# BMS_MAINBOARD.net
KiCad netlist of a schematic drawn in Altium Designer
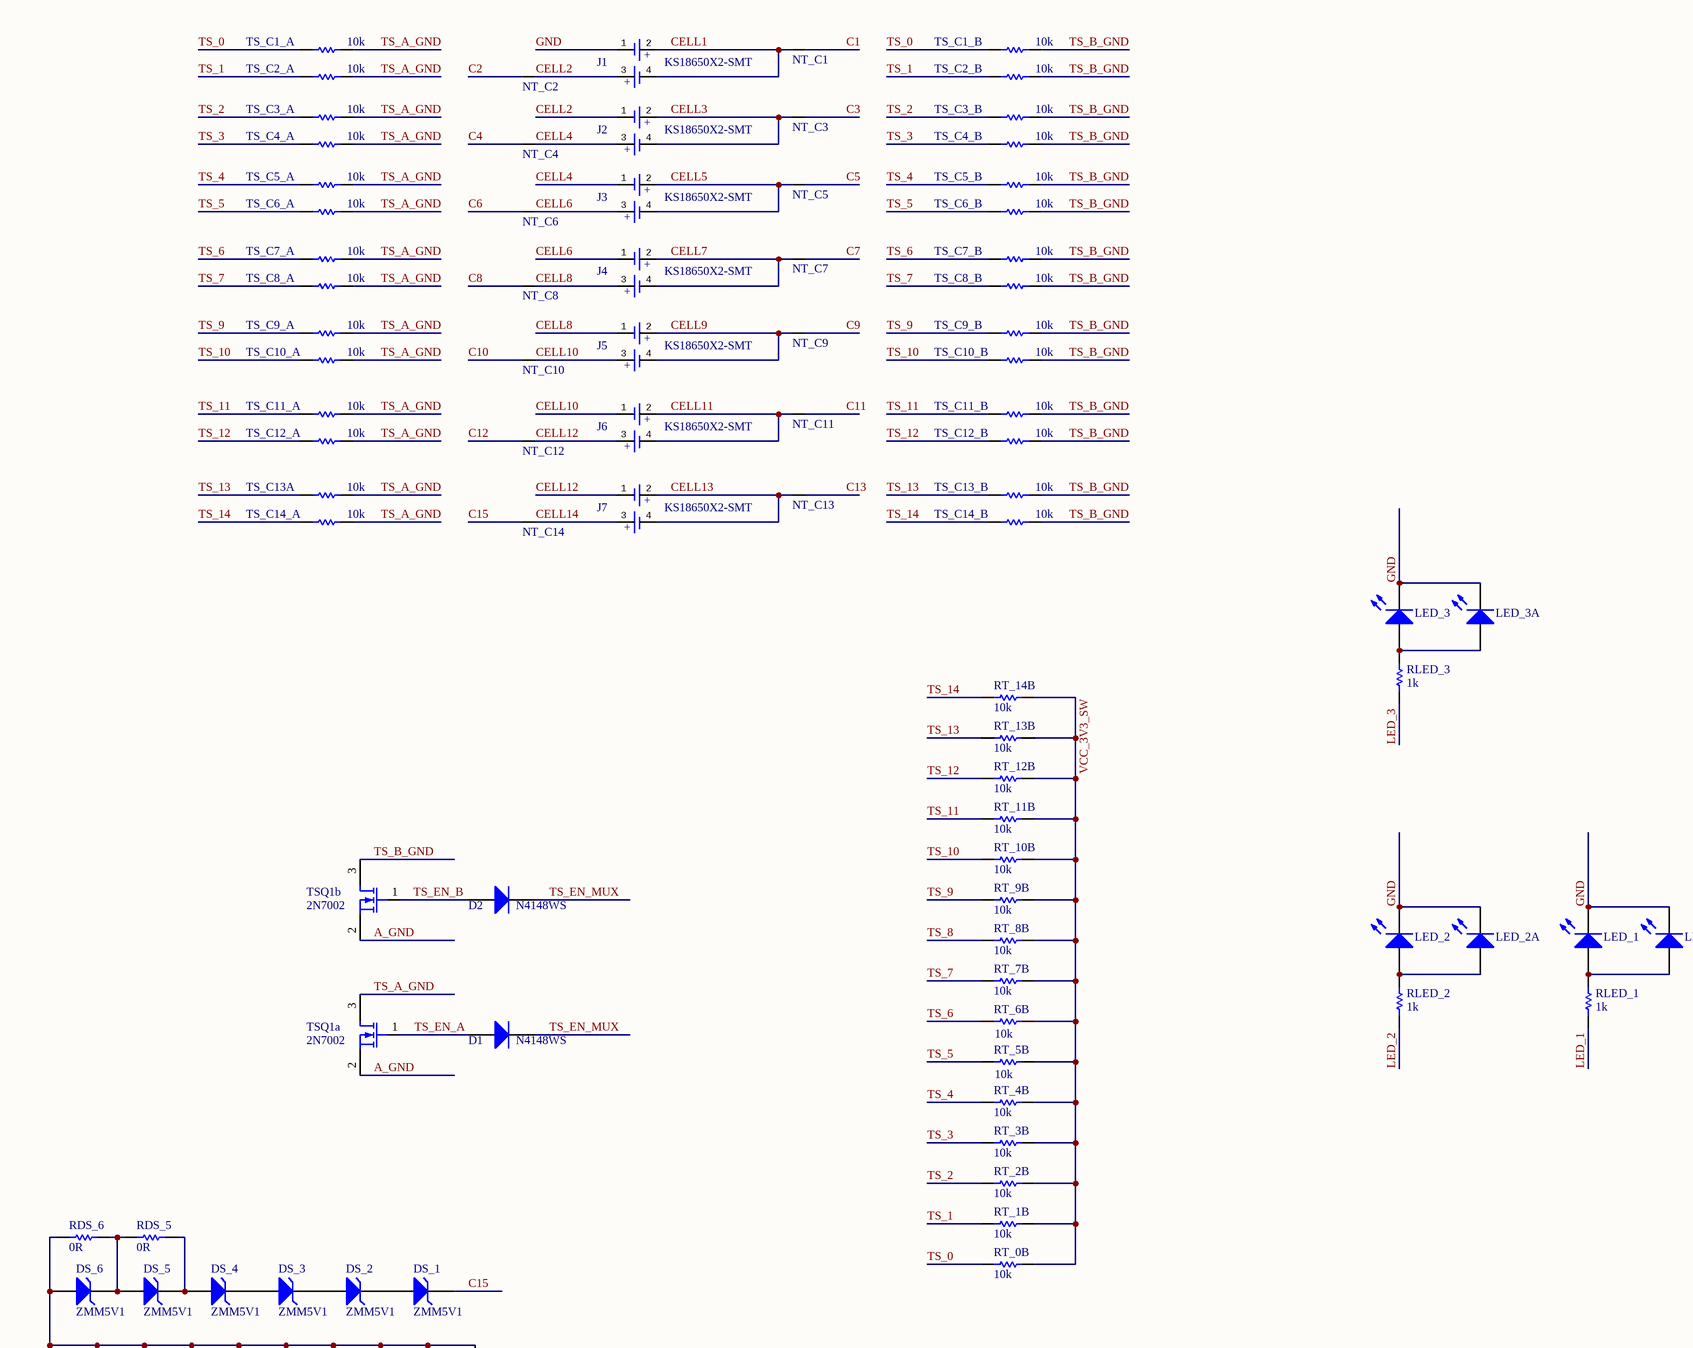
[diagram p0: BMS_MAINBOARD.SchDoc, top left]
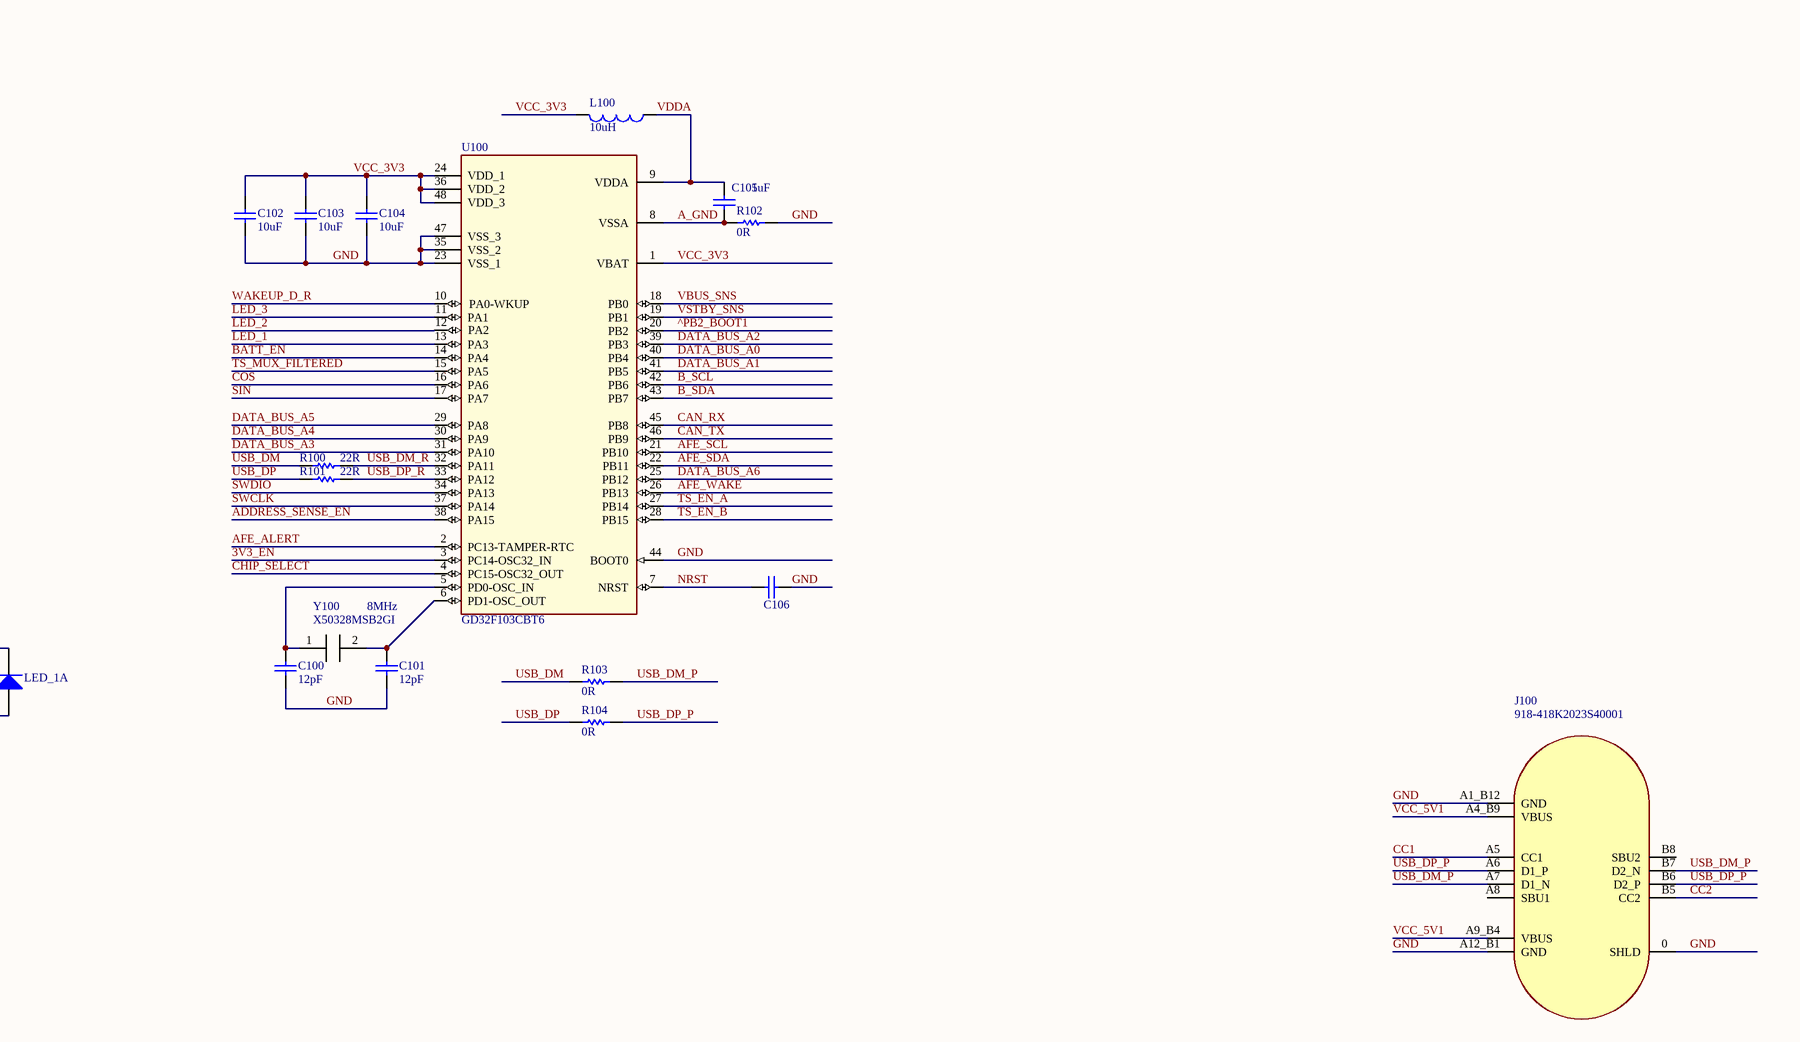
[diagram p1: BMS_MAINBOARD.SchDoc, top right]
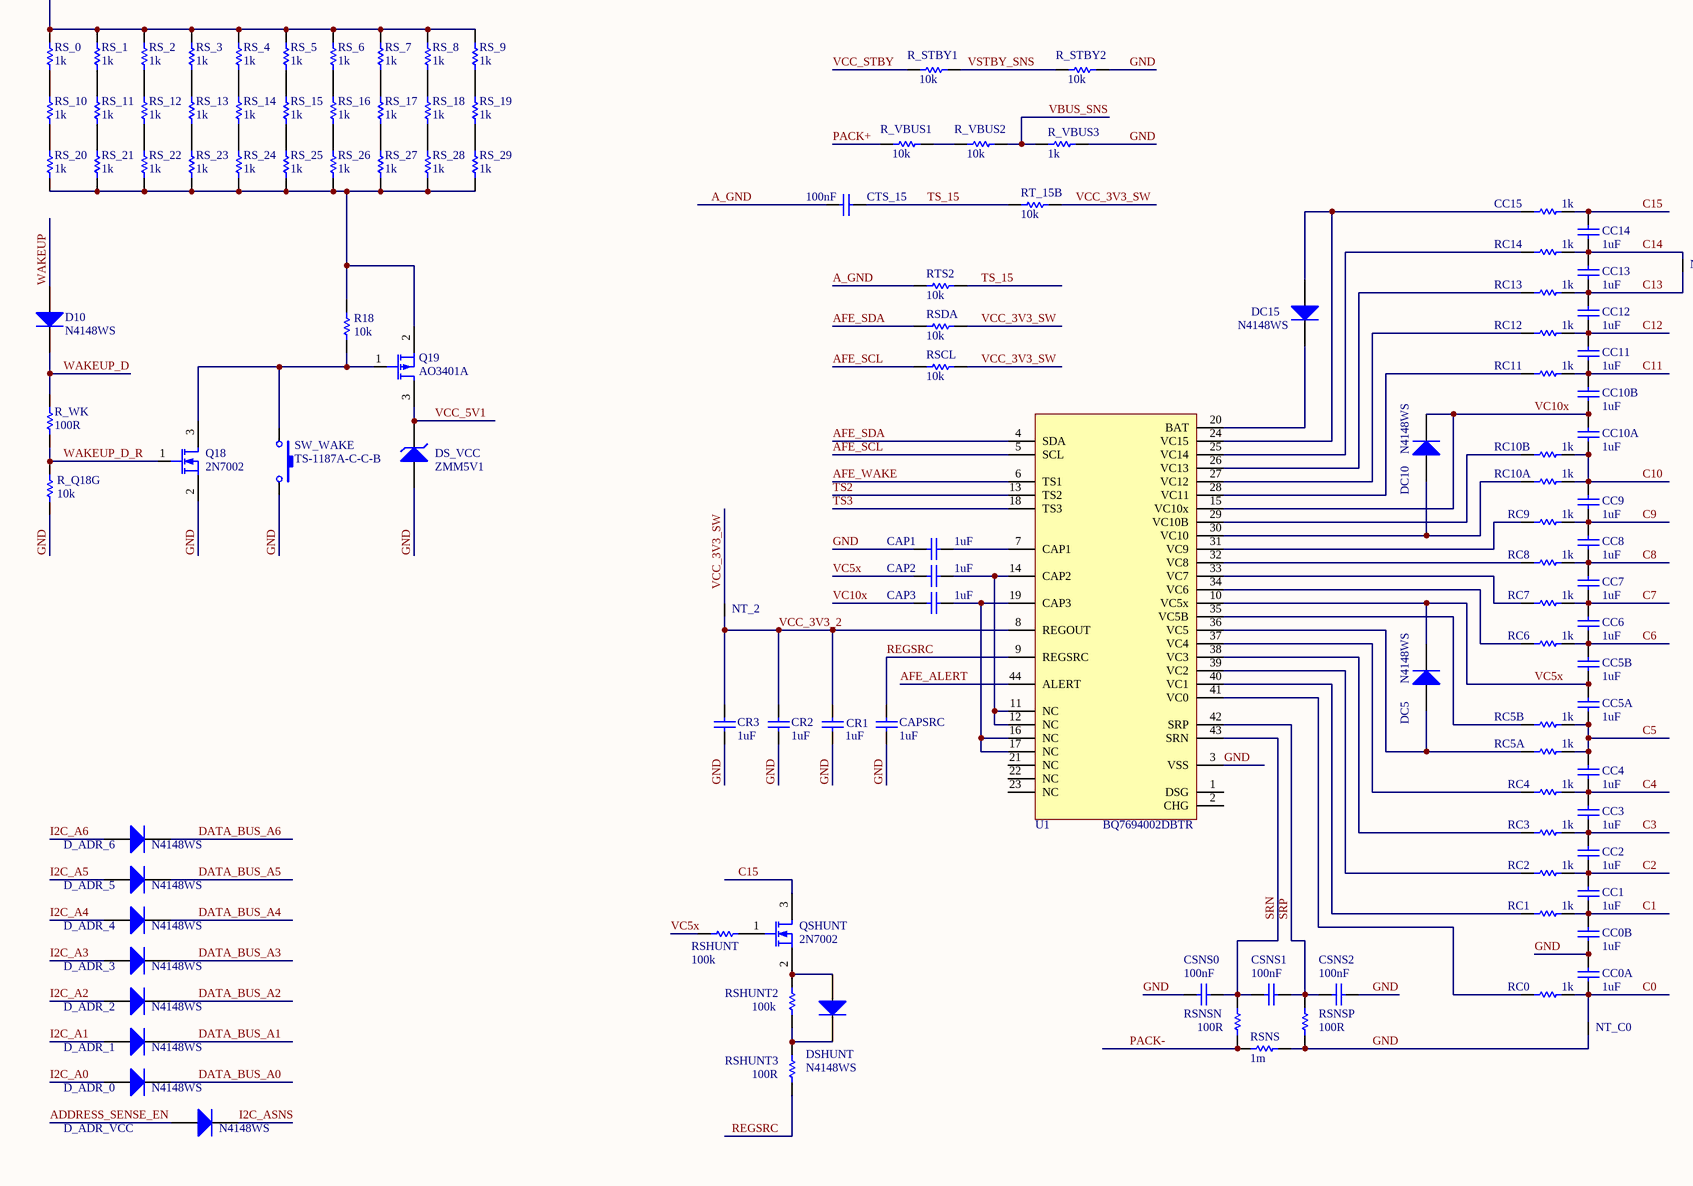
[diagram p2: BMS_MAINBOARD.SchDoc, bottom left]
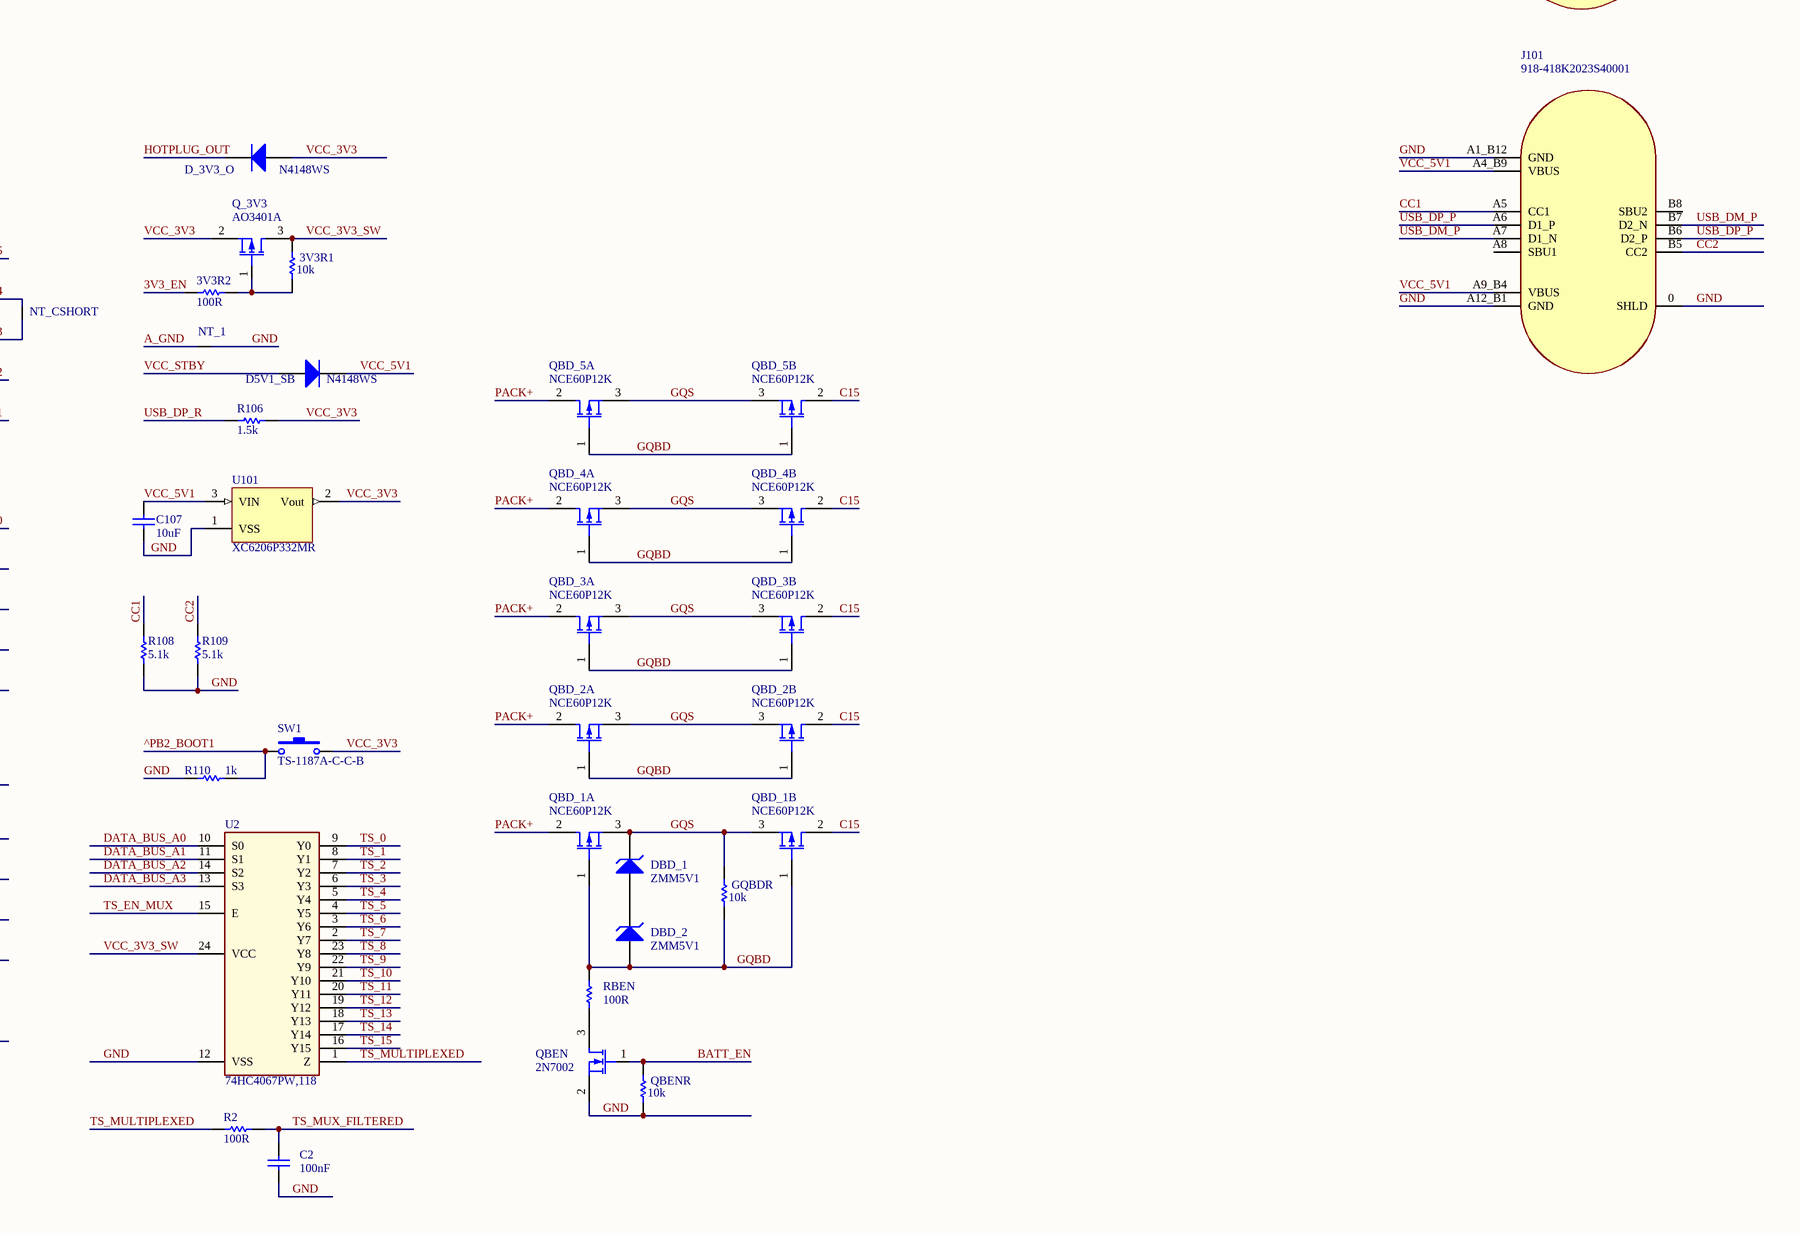
[diagram p3: BMS_MAINBOARD.SchDoc, bottom right]

(export (version "E")
  (design (tool "Eeschema 10.0.6"))
  (components
    (comp (ref "3V3R1")
      (value "10k")
      (footprint "R_0402")
      (description "R - RESISTOR - SMD - 10k - 1% - 0402")
      (fields (field (name "LCSC PART #") "C25744") (field (name "Comment") "0402WGF1002TCE"))
      (libsource (lib "JLC_PCB") (part "0402WGF1002TCE"))
    )
    (comp (ref "3V3R2")
      (value "100R")
      (footprint "R_0402")
      (description "R - RESISTOR - SMD - 100R - 1% - 0402")
      (fields (field (name "LCSC PART #") "C25076") (field (name "Comment") "0402WGF1000TCE"))
      (libsource (lib "JLC_PCB") (part "0402WGF1000TCE"))
    )
    (comp (ref "C2")
      (value "100nF")
      (footprint "C_0402")
      (description "C - CAPACITOR - MLCC - 100nF - 16V - 0402")
      (fields (field (name "LCSC PART #") "C1525") (field (name "Comment") "CL05B104KO5NNNC"))
      (libsource (lib "JLC_PCB") (part "CL05B104KO5NNNC"))
    )
    (comp (ref "C100")
      (value "12pF")
      (footprint "C_0402")
      (description "C - CAPACITOR - MLCC - 12pF - 50V - 0402")
      (fields (field (name "LCSC PART #") "C1547") (field (name "Comment") "0402CG120J500NT"))
      (libsource (lib "JLC_PCB") (part "0402CG120J500NT"))
    )
    (comp (ref "C101")
      (value "12pF")
      (footprint "C_0402")
      (description "C - CAPACITOR - MLCC - 12pF - 50V - 0402")
      (fields (field (name "LCSC PART #") "C1547") (field (name "Comment") "0402CG120J500NT"))
      (libsource (lib "JLC_PCB") (part "0402CG120J500NT"))
    )
    (comp (ref "C102")
      (value "10uF")
      (footprint "C_0402")
      (description "C - CAPACITOR - MLCC - 10uF - 6.3V - 0402")
      (fields (field (name "LCSC PART #") "C15525") (field (name "Comment") "CL05A106MQ5NUNC"))
      (libsource (lib "JLC_PCB") (part "CL05A106MQ5NUNC"))
    )
    (comp (ref "C103")
      (value "10uF")
      (footprint "C_0402")
      (description "C - CAPACITOR - MLCC - 10uF - 6.3V - 0402")
      (fields (field (name "LCSC PART #") "C15525") (field (name "Comment") "CL05A106MQ5NUNC"))
      (libsource (lib "JLC_PCB") (part "CL05A106MQ5NUNC"))
    )
    (comp (ref "C104")
      (value "10uF")
      (footprint "C_0402")
      (description "C - CAPACITOR - MLCC - 10uF - 6.3V - 0402")
      (fields (field (name "LCSC PART #") "C15525") (field (name "Comment") "CL05A106MQ5NUNC"))
      (libsource (lib "JLC_PCB") (part "CL05A106MQ5NUNC"))
    )
    (comp (ref "C105")
      (value "1uF")
      (footprint "C_0402")
      (description "C - CAPACITOR - MLCC - 1uF - 25V - 0402")
      (fields (field (name "LCSC PART #") "C52923") (field (name "Comment") "CL05A105KA5NQNC"))
      (libsource (lib "JLC_PCB") (part "CL05A105KA5NQNC"))
    )
    (comp (ref "C106")
      (value "0402CG101J500NT")
      (footprint "C_0402")
      (description "C - CAPACITOR - MLCC - 100pF - 50V - 0402")
      (fields (field (name "LCSC PART #") "C1546"))
      (libsource (lib "JLC_PCB") (part "0402CG101J500NT"))
    )
    (comp (ref "C107")
      (value "10uF")
      (footprint "C_0402")
      (description "C - CAPACITOR - MLCC - 10uF - 6.3V - 0402")
      (fields (field (name "LCSC PART #") "C15525") (field (name "Comment") "CL05A106MQ5NUNC"))
      (libsource (lib "JLC_PCB") (part "CL05A106MQ5NUNC"))
    )
    (comp (ref "CAP1")
      (value "1uF")
      (footprint "C_0402")
      (description "C - CAPACITOR - MLCC - 1uF - 25V - 0402")
      (fields (field (name "LCSC PART #") "C52923") (field (name "Comment") "CL05A105KA5NQNC"))
      (libsource (lib "JLC_PCB") (part "CL05A105KA5NQNC"))
    )
    (comp (ref "CAP2")
      (value "1uF")
      (footprint "C_0402")
      (description "C - CAPACITOR - MLCC - 1uF - 25V - 0402")
      (fields (field (name "LCSC PART #") "C52923") (field (name "Comment") "CL05A105KA5NQNC"))
      (libsource (lib "JLC_PCB") (part "CL05A105KA5NQNC"))
    )
    (comp (ref "CAP3")
      (value "1uF")
      (footprint "C_0402")
      (description "C - CAPACITOR - MLCC - 1uF - 25V - 0402")
      (fields (field (name "LCSC PART #") "C52923") (field (name "Comment") "CL05A105KA5NQNC"))
      (libsource (lib "JLC_PCB") (part "CL05A105KA5NQNC"))
    )
    (comp (ref "CAPSRC")
      (value "1uF")
      (footprint "C_0402")
      (description "C - CAPACITOR - MLCC - 1uF - 25V - 0402")
      (fields (field (name "LCSC PART #") "C52923") (field (name "Comment") "CL05A105KA5NQNC"))
      (libsource (lib "JLC_PCB") (part "CL05A105KA5NQNC"))
    )
    (comp (ref "CC0A")
      (value "1uF")
      (footprint "C_0402")
      (description "C - CAPACITOR - MLCC - 1uF - 25V - 0402")
      (fields (field (name "LCSC PART #") "C52923") (field (name "Comment") "CL05A105KA5NQNC"))
      (libsource (lib "JLC_PCB") (part "CL05A105KA5NQNC"))
    )
    (comp (ref "CC0B")
      (value "1uF")
      (footprint "C_0402")
      (description "C - CAPACITOR - MLCC - 1uF - 25V - 0402")
      (fields (field (name "LCSC PART #") "C52923") (field (name "Comment") "CL05A105KA5NQNC"))
      (libsource (lib "JLC_PCB") (part "CL05A105KA5NQNC"))
    )
    (comp (ref "CC1")
      (value "1uF")
      (footprint "C_0402")
      (description "C - CAPACITOR - MLCC - 1uF - 25V - 0402")
      (fields (field (name "LCSC PART #") "C52923") (field (name "Comment") "CL05A105KA5NQNC"))
      (libsource (lib "JLC_PCB") (part "CL05A105KA5NQNC"))
    )
    (comp (ref "CC2")
      (value "1uF")
      (footprint "C_0402")
      (description "C - CAPACITOR - MLCC - 1uF - 25V - 0402")
      (fields (field (name "LCSC PART #") "C52923") (field (name "Comment") "CL05A105KA5NQNC"))
      (libsource (lib "JLC_PCB") (part "CL05A105KA5NQNC"))
    )
    (comp (ref "CC3")
      (value "1uF")
      (footprint "C_0402")
      (description "C - CAPACITOR - MLCC - 1uF - 25V - 0402")
      (fields (field (name "LCSC PART #") "C52923") (field (name "Comment") "CL05A105KA5NQNC"))
      (libsource (lib "JLC_PCB") (part "CL05A105KA5NQNC"))
    )
    (comp (ref "CC4")
      (value "1uF")
      (footprint "C_0402")
      (description "C - CAPACITOR - MLCC - 1uF - 25V - 0402")
      (fields (field (name "LCSC PART #") "C52923") (field (name "Comment") "CL05A105KA5NQNC"))
      (libsource (lib "JLC_PCB") (part "CL05A105KA5NQNC"))
    )
    (comp (ref "CC5A")
      (value "1uF")
      (footprint "C_0402")
      (description "C - CAPACITOR - MLCC - 1uF - 25V - 0402")
      (fields (field (name "LCSC PART #") "C52923") (field (name "Comment") "CL05A105KA5NQNC"))
      (libsource (lib "JLC_PCB") (part "CL05A105KA5NQNC"))
    )
    (comp (ref "CC5B")
      (value "1uF")
      (footprint "C_0402")
      (description "C - CAPACITOR - MLCC - 1uF - 25V - 0402")
      (fields (field (name "LCSC PART #") "C52923") (field (name "Comment") "CL05A105KA5NQNC"))
      (libsource (lib "JLC_PCB") (part "CL05A105KA5NQNC"))
    )
    (comp (ref "CC6")
      (value "1uF")
      (footprint "C_0402")
      (description "C - CAPACITOR - MLCC - 1uF - 25V - 0402")
      (fields (field (name "LCSC PART #") "C52923") (field (name "Comment") "CL05A105KA5NQNC"))
      (libsource (lib "JLC_PCB") (part "CL05A105KA5NQNC"))
    )
    (comp (ref "CC7")
      (value "1uF")
      (footprint "C_0402")
      (description "C - CAPACITOR - MLCC - 1uF - 25V - 0402")
      (fields (field (name "LCSC PART #") "C52923") (field (name "Comment") "CL05A105KA5NQNC"))
      (libsource (lib "JLC_PCB") (part "CL05A105KA5NQNC"))
    )
    (comp (ref "CC8")
      (value "1uF")
      (footprint "C_0402")
      (description "C - CAPACITOR - MLCC - 1uF - 25V - 0402")
      (fields (field (name "LCSC PART #") "C52923") (field (name "Comment") "CL05A105KA5NQNC"))
      (libsource (lib "JLC_PCB") (part "CL05A105KA5NQNC"))
    )
    (comp (ref "CC9")
      (value "1uF")
      (footprint "C_0402")
      (description "C - CAPACITOR - MLCC - 1uF - 25V - 0402")
      (fields (field (name "LCSC PART #") "C52923") (field (name "Comment") "CL05A105KA5NQNC"))
      (libsource (lib "JLC_PCB") (part "CL05A105KA5NQNC"))
    )
    (comp (ref "CC10A")
      (value "1uF")
      (footprint "C_0402")
      (description "C - CAPACITOR - MLCC - 1uF - 25V - 0402")
      (fields (field (name "LCSC PART #") "C52923") (field (name "Comment") "CL05A105KA5NQNC"))
      (libsource (lib "JLC_PCB") (part "CL05A105KA5NQNC"))
    )
    (comp (ref "CC10B")
      (value "1uF")
      (footprint "C_0402")
      (description "C - CAPACITOR - MLCC - 1uF - 25V - 0402")
      (fields (field (name "LCSC PART #") "C52923") (field (name "Comment") "CL05A105KA5NQNC"))
      (libsource (lib "JLC_PCB") (part "CL05A105KA5NQNC"))
    )
    (comp (ref "CC11")
      (value "1uF")
      (footprint "C_0402")
      (description "C - CAPACITOR - MLCC - 1uF - 25V - 0402")
      (fields (field (name "LCSC PART #") "C52923") (field (name "Comment") "CL05A105KA5NQNC"))
      (libsource (lib "JLC_PCB") (part "CL05A105KA5NQNC"))
    )
    (comp (ref "CC12")
      (value "1uF")
      (footprint "C_0402")
      (description "C - CAPACITOR - MLCC - 1uF - 25V - 0402")
      (fields (field (name "LCSC PART #") "C52923") (field (name "Comment") "CL05A105KA5NQNC"))
      (libsource (lib "JLC_PCB") (part "CL05A105KA5NQNC"))
    )
    (comp (ref "CC13")
      (value "1uF")
      (footprint "C_0402")
      (description "C - CAPACITOR - MLCC - 1uF - 25V - 0402")
      (fields (field (name "LCSC PART #") "C52923") (field (name "Comment") "CL05A105KA5NQNC"))
      (libsource (lib "JLC_PCB") (part "CL05A105KA5NQNC"))
    )
    (comp (ref "CC14")
      (value "1uF")
      (footprint "C_0402")
      (description "C - CAPACITOR - MLCC - 1uF - 25V - 0402")
      (fields (field (name "LCSC PART #") "C52923") (field (name "Comment") "CL05A105KA5NQNC"))
      (libsource (lib "JLC_PCB") (part "CL05A105KA5NQNC"))
    )
    (comp (ref "CC15")
      (value "1k")
      (footprint "R_0402")
      (description "R - RESISTOR - SMD - 1k - 1% - 0402")
      (fields (field (name "LCSC PART #") "C11702") (field (name "Comment") "0402WGF1001TCE"))
      (libsource (lib "JLC_PCB") (part "0402WGF1001TCE"))
    )
    (comp (ref "CR1")
      (value "1uF")
      (footprint "C_0402")
      (description "C - CAPACITOR - MLCC - 1uF - 25V - 0402")
      (fields (field (name "LCSC PART #") "C52923") (field (name "Comment") "CL05A105KA5NQNC"))
      (libsource (lib "JLC_PCB") (part "CL05A105KA5NQNC"))
    )
    (comp (ref "CR2")
      (value "1uF")
      (footprint "C_0402")
      (description "C - CAPACITOR - MLCC - 1uF - 25V - 0402")
      (fields (field (name "LCSC PART #") "C52923") (field (name "Comment") "CL05A105KA5NQNC"))
      (libsource (lib "JLC_PCB") (part "CL05A105KA5NQNC"))
    )
    (comp (ref "CR3")
      (value "1uF")
      (footprint "C_0402")
      (description "C - CAPACITOR - MLCC - 1uF - 25V - 0402")
      (fields (field (name "LCSC PART #") "C52923") (field (name "Comment") "CL05A105KA5NQNC"))
      (libsource (lib "JLC_PCB") (part "CL05A105KA5NQNC"))
    )
    (comp (ref "CSNS0")
      (value "100nF")
      (footprint "C_0402")
      (description "C - CAPACITOR - MLCC - 100nF - 16V - 0402")
      (fields (field (name "LCSC PART #") "C1525") (field (name "Comment") "CL05B104KO5NNNC"))
      (libsource (lib "JLC_PCB") (part "CL05B104KO5NNNC"))
    )
    (comp (ref "CSNS1")
      (value "100nF")
      (footprint "C_0402")
      (description "C - CAPACITOR - MLCC - 100nF - 16V - 0402")
      (fields (field (name "LCSC PART #") "C1525") (field (name "Comment") "CL05B104KO5NNNC"))
      (libsource (lib "JLC_PCB") (part "CL05B104KO5NNNC"))
    )
    (comp (ref "CSNS2")
      (value "100nF")
      (footprint "C_0402")
      (description "C - CAPACITOR - MLCC - 100nF - 16V - 0402")
      (fields (field (name "LCSC PART #") "C1525") (field (name "Comment") "CL05B104KO5NNNC"))
      (libsource (lib "JLC_PCB") (part "CL05B104KO5NNNC"))
    )
    (comp (ref "CTS_15")
      (value "100nF")
      (footprint "C_0402")
      (description "C - CAPACITOR - MLCC - 100nF - 16V - 0402")
      (fields (field (name "LCSC PART #") "C1525") (field (name "Comment") "CL05B104KO5NNNC"))
      (libsource (lib "JLC_PCB") (part "CL05B104KO5NNNC"))
    )
    (comp (ref "D1")
      (value "N4148WS")
      (footprint "SOD-323")
      (description "D - DIODE - FAST TRR - 100V - 150mA - 4ns")
      (fields (field (name "LCSC PART #") "C2128"))
      (libsource (lib "JLC_PCB") (part "N4148WS"))
    )
    (comp (ref "D2")
      (value "N4148WS")
      (footprint "SOD-323")
      (description "D - DIODE - FAST TRR - 100V - 150mA - 4ns")
      (fields (field (name "LCSC PART #") "C2128"))
      (libsource (lib "JLC_PCB") (part "N4148WS"))
    )
    (comp (ref "D5V1_SB")
      (value "N4148WS")
      (footprint "SOD-323")
      (description "D - DIODE - FAST TRR - 100V - 150mA - 4ns")
      (fields (field (name "LCSC PART #") "C2128"))
      (libsource (lib "JLC_PCB") (part "N4148WS"))
    )
    (comp (ref "D10")
      (value "N4148WS")
      (footprint "SOD-323")
      (description "D - DIODE - FAST TRR - 100V - 150mA - 4ns")
      (fields (field (name "LCSC PART #") "C2128"))
      (libsource (lib "JLC_PCB") (part "N4148WS"))
    )
    (comp (ref "DBD_1")
      (value "ZMM5V1")
      (footprint "DO-213AA")
      (description "D - DIODE - ZENER - 5.1V - 500mW")
      (fields (field (name "LCSC PART #") "C8061"))
      (libsource (lib "JLC_PCB") (part "ZMM5V1"))
    )
    (comp (ref "DBD_2")
      (value "ZMM5V1")
      (footprint "DO-213AA")
      (description "D - DIODE - ZENER - 5.1V - 500mW")
      (fields (field (name "LCSC PART #") "C8061"))
      (libsource (lib "JLC_PCB") (part "ZMM5V1"))
    )
    (comp (ref "DC5")
      (value "N4148WS")
      (footprint "SOD-323")
      (description "D - DIODE - FAST TRR - 100V - 150mA - 4ns")
      (fields (field (name "LCSC PART #") "C2128"))
      (libsource (lib "JLC_PCB") (part "N4148WS"))
    )
    (comp (ref "DC10")
      (value "N4148WS")
      (footprint "SOD-323")
      (description "D - DIODE - FAST TRR - 100V - 150mA - 4ns")
      (fields (field (name "LCSC PART #") "C2128"))
      (libsource (lib "JLC_PCB") (part "N4148WS"))
    )
    (comp (ref "DC15")
      (value "N4148WS")
      (footprint "SOD-323")
      (description "D - DIODE - FAST TRR - 100V - 150mA - 4ns")
      (fields (field (name "LCSC PART #") "C2128"))
      (libsource (lib "JLC_PCB") (part "N4148WS"))
    )
    (comp (ref "DSHUNT")
      (value "N4148WS")
      (footprint "SOD-323")
      (description "D - DIODE - FAST TRR - 100V - 150mA - 4ns")
      (fields (field (name "LCSC PART #") "C2128"))
      (libsource (lib "JLC_PCB") (part "N4148WS"))
    )
    (comp (ref "DS_1")
      (value "ZMM5V1")
      (footprint "DO-213AA")
      (description "D - DIODE - ZENER - 5.1V - 500mW")
      (fields (field (name "LCSC PART #") "C8061"))
      (libsource (lib "JLC_PCB") (part "ZMM5V1"))
    )
    (comp (ref "DS_2")
      (value "ZMM5V1")
      (footprint "DO-213AA")
      (description "D - DIODE - ZENER - 5.1V - 500mW")
      (fields (field (name "LCSC PART #") "C8061"))
      (libsource (lib "JLC_PCB") (part "ZMM5V1"))
    )
    (comp (ref "DS_3")
      (value "ZMM5V1")
      (footprint "DO-213AA")
      (description "D - DIODE - ZENER - 5.1V - 500mW")
      (fields (field (name "LCSC PART #") "C8061"))
      (libsource (lib "JLC_PCB") (part "ZMM5V1"))
    )
    (comp (ref "DS_4")
      (value "ZMM5V1")
      (footprint "DO-213AA")
      (description "D - DIODE - ZENER - 5.1V - 500mW")
      (fields (field (name "LCSC PART #") "C8061"))
      (libsource (lib "JLC_PCB") (part "ZMM5V1"))
    )
    (comp (ref "DS_5")
      (value "ZMM5V1")
      (footprint "DO-213AA")
      (description "D - DIODE - ZENER - 5.1V - 500mW")
      (fields (field (name "LCSC PART #") "C8061"))
      (libsource (lib "JLC_PCB") (part "ZMM5V1"))
    )
    (comp (ref "DS_6")
      (value "ZMM5V1")
      (footprint "DO-213AA")
      (description "D - DIODE - ZENER - 5.1V - 500mW")
      (fields (field (name "LCSC PART #") "C8061"))
      (libsource (lib "JLC_PCB") (part "ZMM5V1"))
    )
    (comp (ref "DS_VCC")
      (value "ZMM5V1")
      (footprint "DO-213AA")
      (description "D - DIODE - ZENER - 5.1V - 500mW")
      (fields (field (name "LCSC PART #") "C8061"))
      (libsource (lib "JLC_PCB") (part "ZMM5V1"))
    )
    (comp (ref "D_3V3_O")
      (value "N4148WS")
      (footprint "SOD-323")
      (description "D - DIODE - FAST TRR - 100V - 150mA - 4ns")
      (fields (field (name "LCSC PART #") "C2128"))
      (libsource (lib "JLC_PCB") (part "N4148WS"))
    )
    (comp (ref "D_ADR_0")
      (value "N4148WS")
      (footprint "SOD-323")
      (description "D - DIODE - FAST TRR - 100V - 150mA - 4ns")
      (fields (field (name "LCSC PART #") "C2128"))
      (libsource (lib "JLC_PCB") (part "N4148WS"))
    )
    (comp (ref "D_ADR_1")
      (value "N4148WS")
      (footprint "SOD-323")
      (description "D - DIODE - FAST TRR - 100V - 150mA - 4ns")
      (fields (field (name "LCSC PART #") "C2128"))
      (libsource (lib "JLC_PCB") (part "N4148WS"))
    )
    (comp (ref "D_ADR_2")
      (value "N4148WS")
      (footprint "SOD-323")
      (description "D - DIODE - FAST TRR - 100V - 150mA - 4ns")
      (fields (field (name "LCSC PART #") "C2128"))
      (libsource (lib "JLC_PCB") (part "N4148WS"))
    )
    (comp (ref "D_ADR_3")
      (value "N4148WS")
      (footprint "SOD-323")
      (description "D - DIODE - FAST TRR - 100V - 150mA - 4ns")
      (fields (field (name "LCSC PART #") "C2128"))
      (libsource (lib "JLC_PCB") (part "N4148WS"))
    )
    (comp (ref "D_ADR_4")
      (value "N4148WS")
      (footprint "SOD-323")
      (description "D - DIODE - FAST TRR - 100V - 150mA - 4ns")
      (fields (field (name "LCSC PART #") "C2128"))
      (libsource (lib "JLC_PCB") (part "N4148WS"))
    )
    (comp (ref "D_ADR_5")
      (value "N4148WS")
      (footprint "SOD-323")
      (description "D - DIODE - FAST TRR - 100V - 150mA - 4ns")
      (fields (field (name "LCSC PART #") "C2128"))
      (libsource (lib "JLC_PCB") (part "N4148WS"))
    )
    (comp (ref "D_ADR_6")
      (value "N4148WS")
      (footprint "SOD-323")
      (description "D - DIODE - FAST TRR - 100V - 150mA - 4ns")
      (fields (field (name "LCSC PART #") "C2128"))
      (libsource (lib "JLC_PCB") (part "N4148WS"))
    )
    (comp (ref "D_ADR_VCC")
      (value "N4148WS")
      (footprint "SOD-323")
      (description "D - DIODE - FAST TRR - 100V - 150mA - 4ns")
      (fields (field (name "LCSC PART #") "C2128"))
      (libsource (lib "JLC_PCB") (part "N4148WS"))
    )
    (comp (ref "GQBDR")
      (value "10k")
      (footprint "R_0402")
      (description "R - RESISTOR - SMD - 10k - 1% - 0402")
      (fields (field (name "LCSC PART #") "C25744") (field (name "Comment") "0402WGF1002TCE"))
      (libsource (lib "JLC_PCB") (part "0402WGF1002TCE"))
    )
    (comp (ref "J1")
      (value "KS18650X2-SMT")
      (footprint "KS18650X2-SMT")
      (description "J - JACK - SMT Battery Holder 18650X2 Cells")
      (libsource (lib "JLC_PCB") (part "KS18650X2-SMT"))
    )
    (comp (ref "J2")
      (value "KS18650X2-SMT")
      (footprint "KS18650X2-SMT")
      (description "J - JACK - SMT Battery Holder 18650X2 Cells")
      (libsource (lib "JLC_PCB") (part "KS18650X2-SMT"))
    )
    (comp (ref "J3")
      (value "KS18650X2-SMT")
      (footprint "KS18650X2-SMT")
      (description "J - JACK - SMT Battery Holder 18650X2 Cells")
      (libsource (lib "JLC_PCB") (part "KS18650X2-SMT"))
    )
    (comp (ref "J4")
      (value "KS18650X2-SMT")
      (footprint "KS18650X2-SMT")
      (description "J - JACK - SMT Battery Holder 18650X2 Cells")
      (libsource (lib "JLC_PCB") (part "KS18650X2-SMT"))
    )
    (comp (ref "J5")
      (value "KS18650X2-SMT")
      (footprint "KS18650X2-SMT")
      (description "J - JACK - SMT Battery Holder 18650X2 Cells")
      (libsource (lib "JLC_PCB") (part "KS18650X2-SMT"))
    )
    (comp (ref "J6")
      (value "KS18650X2-SMT")
      (footprint "KS18650X2-SMT")
      (description "J - JACK - SMT Battery Holder 18650X2 Cells")
      (libsource (lib "JLC_PCB") (part "KS18650X2-SMT"))
    )
    (comp (ref "J7")
      (value "KS18650X2-SMT")
      (footprint "KS18650X2-SMT")
      (description "J - JACK - SMT Battery Holder 18650X2 Cells")
      (libsource (lib "JLC_PCB") (part "KS18650X2-SMT"))
    )
    (comp (ref "J100")
      (value "918-418K2023S40001")
      (footprint "DX07S016JA1R1500")
      (description "J - JACK - USB - Type C - Recepticle - SMT - 90°")
      (fields (field (name "LCSC PART #") "C167321"))
      (libsource (lib "JLC_PCB") (part "918-418K2023S40001"))
    )
    (comp (ref "J101")
      (value "918-418K2023S40001")
      (footprint "DX07S016JA1R1500")
      (description "J - JACK - USB - Type C - Recepticle - SMT - 90°")
      (fields (field (name "LCSC PART #") "C167321"))
      (libsource (lib "JLC_PCB") (part "918-418K2023S40001"))
    )
    (comp (ref "L100")
      (value "10uH")
      (footprint "L_0603")
      (description "L - INDUCTOR - 10uH - 0603")
      (fields (field (name "LCSC PART #") "C1035") (field (name "Comment") "SDFL1608S100KTF"))
      (libsource (lib "JLC_PCB") (part "SDFL1608S100KTF"))
    )
    (comp (ref "LED_1")
      (value "19-21UYC/S530-A4/TR8")
      (footprint "D_0603")
      (description "D - LED - 0603 - Yellow (Sodium)")
      (fields (field (name "LCSC PART #") "C409441"))
      (libsource (lib "JLC_PCB") (part "19-21UYC/S530-A4/TR8"))
    )
    (comp (ref "LED_1A")
      (value "19-21UYC/S530-A4/TR8")
      (footprint "D_0603")
      (description "D - LED - 0603 - Yellow (Sodium)")
      (fields (field (name "LCSC PART #") "C409441"))
      (libsource (lib "JLC_PCB") (part "19-21UYC/S530-A4/TR8"))
    )
    (comp (ref "LED_2")
      (value "19-21UYC/S530-A4/TR8")
      (footprint "D_0603")
      (description "D - LED - 0603 - Yellow (Sodium)")
      (fields (field (name "LCSC PART #") "C409441"))
      (libsource (lib "JLC_PCB") (part "19-21UYC/S530-A4/TR8"))
    )
    (comp (ref "LED_2A")
      (value "19-21UYC/S530-A4/TR8")
      (footprint "D_0603")
      (description "D - LED - 0603 - Yellow (Sodium)")
      (fields (field (name "LCSC PART #") "C409441"))
      (libsource (lib "JLC_PCB") (part "19-21UYC/S530-A4/TR8"))
    )
    (comp (ref "LED_3")
      (value "19-21UYC/S530-A4/TR8")
      (footprint "D_0603")
      (description "D - LED - 0603 - Yellow (Sodium)")
      (fields (field (name "LCSC PART #") "C409441"))
      (libsource (lib "JLC_PCB") (part "19-21UYC/S530-A4/TR8"))
    )
    (comp (ref "LED_3A")
      (value "19-21UYC/S530-A4/TR8")
      (footprint "D_0603")
      (description "D - LED - 0603 - Yellow (Sodium)")
      (fields (field (name "LCSC PART #") "C409441"))
      (libsource (lib "JLC_PCB") (part "19-21UYC/S530-A4/TR8"))
    )
    (comp (ref "NT_1")
      (value "0")
      (footprint "NET_TIE")
      (description "R - Net Tie")
      (libsource (lib "JLC_PCB") (part "NET_TIE"))
    )
    (comp (ref "NT_2")
      (value "0")
      (footprint "NET_TIE")
      (description "R - Net Tie")
      (libsource (lib "JLC_PCB") (part "NET_TIE"))
    )
    (comp (ref "NT_C0")
      (value "0")
      (footprint "NET_TIE")
      (description "R - Net Tie")
      (libsource (lib "JLC_PCB") (part "NET_TIE"))
    )
    (comp (ref "NT_C1")
      (value "0")
      (footprint "NET_TIE")
      (description "R - Net Tie")
      (libsource (lib "JLC_PCB") (part "NET_TIE"))
    )
    (comp (ref "NT_C2")
      (value "0")
      (footprint "NET_TIE")
      (description "R - Net Tie")
      (libsource (lib "JLC_PCB") (part "NET_TIE"))
    )
    (comp (ref "NT_C3")
      (value "0")
      (footprint "NET_TIE")
      (description "R - Net Tie")
      (libsource (lib "JLC_PCB") (part "NET_TIE"))
    )
    (comp (ref "NT_C4")
      (value "0")
      (footprint "NET_TIE")
      (description "R - Net Tie")
      (libsource (lib "JLC_PCB") (part "NET_TIE"))
    )
    (comp (ref "NT_C5")
      (value "0")
      (footprint "NET_TIE")
      (description "R - Net Tie")
      (libsource (lib "JLC_PCB") (part "NET_TIE"))
    )
    (comp (ref "NT_C6")
      (value "0")
      (footprint "NET_TIE")
      (description "R - Net Tie")
      (libsource (lib "JLC_PCB") (part "NET_TIE"))
    )
    (comp (ref "NT_C7")
      (value "0")
      (footprint "NET_TIE")
      (description "R - Net Tie")
      (libsource (lib "JLC_PCB") (part "NET_TIE"))
    )
    (comp (ref "NT_C8")
      (value "0")
      (footprint "NET_TIE")
      (description "R - Net Tie")
      (libsource (lib "JLC_PCB") (part "NET_TIE"))
    )
    (comp (ref "NT_C9")
      (value "0")
      (footprint "NET_TIE")
      (description "R - Net Tie")
      (libsource (lib "JLC_PCB") (part "NET_TIE"))
    )
    (comp (ref "NT_C10")
      (value "0")
      (footprint "NET_TIE")
      (description "R - Net Tie")
      (libsource (lib "JLC_PCB") (part "NET_TIE"))
    )
    (comp (ref "NT_C11")
      (value "0")
      (footprint "NET_TIE")
      (description "R - Net Tie")
      (libsource (lib "JLC_PCB") (part "NET_TIE"))
    )
    (comp (ref "NT_C12")
      (value "0")
      (footprint "NET_TIE")
      (description "R - Net Tie")
      (libsource (lib "JLC_PCB") (part "NET_TIE"))
    )
    (comp (ref "NT_C13")
      (value "0")
      (footprint "NET_TIE")
      (description "R - Net Tie")
      (libsource (lib "JLC_PCB") (part "NET_TIE"))
    )
    (comp (ref "NT_C14")
      (value "0")
      (footprint "NET_TIE")
      (description "R - Net Tie")
      (libsource (lib "JLC_PCB") (part "NET_TIE"))
    )
    (comp (ref "NT_CSHORT")
      (value "0")
      (footprint "NET_TIE")
      (description "R - Net Tie")
      (libsource (lib "JLC_PCB") (part "NET_TIE"))
    )
    (comp (ref "Q18")
      (value "2N7002")
      (footprint "TO-236AB")
      (description "Q - TRANSISTOR - MOSFET (N) - 60V - 200mW")
      (fields (field (name "LCSC PART #") "C8545"))
      (libsource (lib "JLC_PCB") (part "2N7002"))
    )
    (comp (ref "Q19")
      (value "AO3401A")
      (footprint "TO-236AB")
      (description "Q - TRANSISTOR - MOSFET (P) - 30V - 1.4A - 0.44 Ohm")
      (fields (field (name "LCSC PART #") "C15127"))
      (libsource (lib "JLC_PCB") (part "AO3401A"))
    )
    (comp (ref "QBD_1A")
      (value "NCE60P12K")
      (footprint "TO-252AA")
      (description "Q - TRANSISTOR - MOSFET (P) - 60V - 12A - 0.1R")
      (fields (field (name "LCSC PART #") "C326372"))
      (libsource (lib "JLC_PCB") (part "NCE60P12K"))
    )
    (comp (ref "QBD_1B")
      (value "NCE60P12K")
      (footprint "TO-252AA")
      (description "Q - TRANSISTOR - MOSFET (P) - 60V - 12A - 0.1R")
      (fields (field (name "LCSC PART #") "C326372"))
      (libsource (lib "JLC_PCB") (part "NCE60P12K"))
    )
    (comp (ref "QBD_2A")
      (value "NCE60P12K")
      (footprint "TO-252AA")
      (description "Q - TRANSISTOR - MOSFET (P) - 60V - 12A - 0.1R")
      (fields (field (name "LCSC PART #") "C326372"))
      (libsource (lib "JLC_PCB") (part "NCE60P12K"))
    )
    (comp (ref "QBD_2B")
      (value "NCE60P12K")
      (footprint "TO-252AA")
      (description "Q - TRANSISTOR - MOSFET (P) - 60V - 12A - 0.1R")
      (fields (field (name "LCSC PART #") "C326372"))
      (libsource (lib "JLC_PCB") (part "NCE60P12K"))
    )
    (comp (ref "QBD_3A")
      (value "NCE60P12K")
      (footprint "TO-252AA")
      (description "Q - TRANSISTOR - MOSFET (P) - 60V - 12A - 0.1R")
      (fields (field (name "LCSC PART #") "C326372"))
      (libsource (lib "JLC_PCB") (part "NCE60P12K"))
    )
    (comp (ref "QBD_3B")
      (value "NCE60P12K")
      (footprint "TO-252AA")
      (description "Q - TRANSISTOR - MOSFET (P) - 60V - 12A - 0.1R")
      (fields (field (name "LCSC PART #") "C326372"))
      (libsource (lib "JLC_PCB") (part "NCE60P12K"))
    )
    (comp (ref "QBD_4A")
      (value "NCE60P12K")
      (footprint "TO-252AA")
      (description "Q - TRANSISTOR - MOSFET (P) - 60V - 12A - 0.1R")
      (fields (field (name "LCSC PART #") "C326372"))
      (libsource (lib "JLC_PCB") (part "NCE60P12K"))
    )
    (comp (ref "QBD_4B")
      (value "NCE60P12K")
      (footprint "TO-252AA")
      (description "Q - TRANSISTOR - MOSFET (P) - 60V - 12A - 0.1R")
      (fields (field (name "LCSC PART #") "C326372"))
      (libsource (lib "JLC_PCB") (part "NCE60P12K"))
    )
    (comp (ref "QBD_5A")
      (value "NCE60P12K")
      (footprint "TO-252AA")
      (description "Q - TRANSISTOR - MOSFET (P) - 60V - 12A - 0.1R")
      (fields (field (name "LCSC PART #") "C326372"))
      (libsource (lib "JLC_PCB") (part "NCE60P12K"))
    )
    (comp (ref "QBD_5B")
      (value "NCE60P12K")
      (footprint "TO-252AA")
      (description "Q - TRANSISTOR - MOSFET (P) - 60V - 12A - 0.1R")
      (fields (field (name "LCSC PART #") "C326372"))
      (libsource (lib "JLC_PCB") (part "NCE60P12K"))
    )
    (comp (ref "QBEN")
      (value "2N7002")
      (footprint "TO-236AB")
      (description "Q - TRANSISTOR - MOSFET (N) - 60V - 200mW")
      (fields (field (name "LCSC PART #") "C8545"))
      (libsource (lib "JLC_PCB") (part "2N7002"))
    )
    (comp (ref "QBENR")
      (value "10k")
      (footprint "R_0402")
      (description "R - RESISTOR - SMD - 10k - 1% - 0402")
      (fields (field (name "LCSC PART #") "C25744") (field (name "Comment") "0402WGF1002TCE"))
      (libsource (lib "JLC_PCB") (part "0402WGF1002TCE"))
    )
    (comp (ref "QSHUNT")
      (value "2N7002")
      (footprint "TO-236AB")
      (description "Q - TRANSISTOR - MOSFET (N) - 60V - 200mW")
      (fields (field (name "LCSC PART #") "C8545"))
      (libsource (lib "JLC_PCB") (part "2N7002"))
    )
    (comp (ref "Q_3V3")
      (value "AO3401A")
      (footprint "TO-236AB")
      (description "Q - TRANSISTOR - MOSFET (P) - 30V - 1.4A - 0.44 Ohm")
      (fields (field (name "LCSC PART #") "C15127"))
      (libsource (lib "JLC_PCB") (part "AO3401A"))
    )
    (comp (ref "R2")
      (value "100R")
      (footprint "R_0402")
      (description "R - RESISTOR - SMD - 100R - 1% - 0402")
      (fields (field (name "LCSC PART #") "C25076") (field (name "Comment") "0402WGF1000TCE"))
      (libsource (lib "JLC_PCB") (part "0402WGF1000TCE"))
    )
    (comp (ref "R18")
      (value "10k")
      (footprint "R_0402")
      (description "R - RESISTOR - SMD - 10k - 1% - 0402")
      (fields (field (name "LCSC PART #") "C25744") (field (name "Comment") "0402WGF1002TCE"))
      (libsource (lib "JLC_PCB") (part "0402WGF1002TCE"))
    )
    (comp (ref "R100")
      (value "22R")
      (footprint "R_0402")
      (description "R - RESISTOR - SMD - 22R - 1% - 0402")
      (fields (field (name "LCSC PART #") "C25092") (field (name "Comment") "0402WGF220JTCE"))
      (libsource (lib "JLC_PCB") (part "0402WGF220JTCE"))
    )
    (comp (ref "R101")
      (value "22R")
      (footprint "R_0402")
      (description "R - RESISTOR - SMD - 22R - 1% - 0402")
      (fields (field (name "LCSC PART #") "C25092") (field (name "Comment") "0402WGF220JTCE"))
      (libsource (lib "JLC_PCB") (part "0402WGF220JTCE"))
    )
    (comp (ref "R102")
      (value "0R")
      (footprint "R_0402")
      (description "R - RESISTOR - SMD - 0R - 1% - 0402")
      (fields (field (name "LCSC PART #") "C17168") (field (name "Comment") "0402WGF0000TCE"))
      (libsource (lib "JLC_PCB") (part "0402WGF0000TCE"))
    )
    (comp (ref "R103")
      (value "0R")
      (footprint "R_0402")
      (description "R - RESISTOR - SMD - 0R - 1% - 0402")
      (fields (field (name "LCSC PART #") "C17168") (field (name "Comment") "0402WGF0000TCE"))
      (libsource (lib "JLC_PCB") (part "0402WGF0000TCE"))
    )
    (comp (ref "R104")
      (value "0R")
      (footprint "R_0402")
      (description "R - RESISTOR - SMD - 0R - 1% - 0402")
      (fields (field (name "LCSC PART #") "C17168") (field (name "Comment") "0402WGF0000TCE"))
      (libsource (lib "JLC_PCB") (part "0402WGF0000TCE"))
    )
    (comp (ref "R106")
      (value "1.5k")
      (footprint "R_0402")
      (description "R - RESISTOR - SMD - 1.5k - 1% - 0402")
      (fields (field (name "LCSC PART #") "C25867") (field (name "Comment") "0402WGF1501TCE"))
      (libsource (lib "JLC_PCB") (part "0402WGF1501TCE"))
    )
    (comp (ref "R108")
      (value "5.1k")
      (footprint "R_0402")
      (description "R - RESISTOR - SMD - 5.1k - 1% - 0402")
      (fields (field (name "LCSC PART #") "C25905") (field (name "Comment") "0402WGF5101TCE"))
      (libsource (lib "JLC_PCB") (part "0402WGF5101TCE"))
    )
    (comp (ref "R109")
      (value "5.1k")
      (footprint "R_0402")
      (description "R - RESISTOR - SMD - 5.1k - 1% - 0402")
      (fields (field (name "LCSC PART #") "C25905") (field (name "Comment") "0402WGF5101TCE"))
      (libsource (lib "JLC_PCB") (part "0402WGF5101TCE"))
    )
    (comp (ref "R110")
      (value "1k")
      (footprint "R_0402")
      (description "R - RESISTOR - SMD - 1k - 1% - 0402")
      (fields (field (name "LCSC PART #") "C11702") (field (name "Comment") "0402WGF1001TCE"))
      (libsource (lib "JLC_PCB") (part "0402WGF1001TCE"))
    )
    (comp (ref "RBEN")
      (value "100R")
      (footprint "R_0402")
      (description "R - RESISTOR - SMD - 100R - 1% - 0402")
      (fields (field (name "LCSC PART #") "C25076") (field (name "Comment") "0402WGF1000TCE"))
      (libsource (lib "JLC_PCB") (part "0402WGF1000TCE"))
    )
    (comp (ref "RC0")
      (value "1k")
      (footprint "R_0402")
      (description "R - RESISTOR - SMD - 1k - 1% - 0402")
      (fields (field (name "LCSC PART #") "C11702") (field (name "Comment") "0402WGF1001TCE"))
      (libsource (lib "JLC_PCB") (part "0402WGF1001TCE"))
    )
    (comp (ref "RC1")
      (value "1k")
      (footprint "R_0402")
      (description "R - RESISTOR - SMD - 1k - 1% - 0402")
      (fields (field (name "LCSC PART #") "C11702") (field (name "Comment") "0402WGF1001TCE"))
      (libsource (lib "JLC_PCB") (part "0402WGF1001TCE"))
    )
    (comp (ref "RC2")
      (value "1k")
      (footprint "R_0402")
      (description "R - RESISTOR - SMD - 1k - 1% - 0402")
      (fields (field (name "LCSC PART #") "C11702") (field (name "Comment") "0402WGF1001TCE"))
      (libsource (lib "JLC_PCB") (part "0402WGF1001TCE"))
    )
    (comp (ref "RC3")
      (value "1k")
      (footprint "R_0402")
      (description "R - RESISTOR - SMD - 1k - 1% - 0402")
      (fields (field (name "LCSC PART #") "C11702") (field (name "Comment") "0402WGF1001TCE"))
      (libsource (lib "JLC_PCB") (part "0402WGF1001TCE"))
    )
    (comp (ref "RC4")
      (value "1k")
      (footprint "R_0402")
      (description "R - RESISTOR - SMD - 1k - 1% - 0402")
      (fields (field (name "LCSC PART #") "C11702") (field (name "Comment") "0402WGF1001TCE"))
      (libsource (lib "JLC_PCB") (part "0402WGF1001TCE"))
    )
    (comp (ref "RC5A")
      (value "1k")
      (footprint "R_0402")
      (description "R - RESISTOR - SMD - 1k - 1% - 0402")
      (fields (field (name "LCSC PART #") "C11702") (field (name "Comment") "0402WGF1001TCE"))
      (libsource (lib "JLC_PCB") (part "0402WGF1001TCE"))
    )
    (comp (ref "RC5B")
      (value "1k")
      (footprint "R_0402")
      (description "R - RESISTOR - SMD - 1k - 1% - 0402")
      (fields (field (name "LCSC PART #") "C11702") (field (name "Comment") "0402WGF1001TCE"))
      (libsource (lib "JLC_PCB") (part "0402WGF1001TCE"))
    )
    (comp (ref "RC6")
      (value "1k")
      (footprint "R_0402")
      (description "R - RESISTOR - SMD - 1k - 1% - 0402")
      (fields (field (name "LCSC PART #") "C11702") (field (name "Comment") "0402WGF1001TCE"))
      (libsource (lib "JLC_PCB") (part "0402WGF1001TCE"))
    )
    (comp (ref "RC7")
      (value "1k")
      (footprint "R_0402")
      (description "R - RESISTOR - SMD - 1k - 1% - 0402")
      (fields (field (name "LCSC PART #") "C11702") (field (name "Comment") "0402WGF1001TCE"))
      (libsource (lib "JLC_PCB") (part "0402WGF1001TCE"))
    )
    (comp (ref "RC8")
      (value "1k")
      (footprint "R_0402")
      (description "R - RESISTOR - SMD - 1k - 1% - 0402")
      (fields (field (name "LCSC PART #") "C11702") (field (name "Comment") "0402WGF1001TCE"))
      (libsource (lib "JLC_PCB") (part "0402WGF1001TCE"))
    )
    (comp (ref "RC9")
      (value "1k")
      (footprint "R_0402")
      (description "R - RESISTOR - SMD - 1k - 1% - 0402")
      (fields (field (name "LCSC PART #") "C11702") (field (name "Comment") "0402WGF1001TCE"))
      (libsource (lib "JLC_PCB") (part "0402WGF1001TCE"))
    )
    (comp (ref "RC10A")
      (value "1k")
      (footprint "R_0402")
      (description "R - RESISTOR - SMD - 1k - 1% - 0402")
      (fields (field (name "LCSC PART #") "C11702") (field (name "Comment") "0402WGF1001TCE"))
      (libsource (lib "JLC_PCB") (part "0402WGF1001TCE"))
    )
    (comp (ref "RC10B")
      (value "1k")
      (footprint "R_0402")
      (description "R - RESISTOR - SMD - 1k - 1% - 0402")
      (fields (field (name "LCSC PART #") "C11702") (field (name "Comment") "0402WGF1001TCE"))
      (libsource (lib "JLC_PCB") (part "0402WGF1001TCE"))
    )
    (comp (ref "RC11")
      (value "1k")
      (footprint "R_0402")
      (description "R - RESISTOR - SMD - 1k - 1% - 0402")
      (fields (field (name "LCSC PART #") "C11702") (field (name "Comment") "0402WGF1001TCE"))
      (libsource (lib "JLC_PCB") (part "0402WGF1001TCE"))
    )
    (comp (ref "RC12")
      (value "1k")
      (footprint "R_0402")
      (description "R - RESISTOR - SMD - 1k - 1% - 0402")
      (fields (field (name "LCSC PART #") "C11702") (field (name "Comment") "0402WGF1001TCE"))
      (libsource (lib "JLC_PCB") (part "0402WGF1001TCE"))
    )
    (comp (ref "RC13")
      (value "1k")
      (footprint "R_0402")
      (description "R - RESISTOR - SMD - 1k - 1% - 0402")
      (fields (field (name "LCSC PART #") "C11702") (field (name "Comment") "0402WGF1001TCE"))
      (libsource (lib "JLC_PCB") (part "0402WGF1001TCE"))
    )
    (comp (ref "RC14")
      (value "1k")
      (footprint "R_0402")
      (description "R - RESISTOR - SMD - 1k - 1% - 0402")
      (fields (field (name "LCSC PART #") "C11702") (field (name "Comment") "0402WGF1001TCE"))
      (libsource (lib "JLC_PCB") (part "0402WGF1001TCE"))
    )
    (comp (ref "RDS_5")
      (value "0R")
      (footprint "R_0402")
      (description "R - RESISTOR - SMD - 0R - 1% - 0402")
      (fields (field (name "LCSC PART #") "C17168") (field (name "Comment") "0402WGF0000TCE"))
      (libsource (lib "JLC_PCB") (part "0402WGF0000TCE"))
    )
    (comp (ref "RDS_6")
      (value "0R")
      (footprint "R_0402")
      (description "R - RESISTOR - SMD - 0R - 1% - 0402")
      (fields (field (name "LCSC PART #") "C17168") (field (name "Comment") "0402WGF0000TCE"))
      (libsource (lib "JLC_PCB") (part "0402WGF0000TCE"))
    )
    (comp (ref "RLED_1")
      (value "1k")
      (footprint "R_0402")
      (description "R - RESISTOR - SMD - 1k - 1% - 0402")
      (fields (field (name "LCSC PART #") "C11702") (field (name "Comment") "0402WGF1001TCE"))
      (libsource (lib "JLC_PCB") (part "0402WGF1001TCE"))
    )
    (comp (ref "RLED_2")
      (value "1k")
      (footprint "R_0402")
      (description "R - RESISTOR - SMD - 1k - 1% - 0402")
      (fields (field (name "LCSC PART #") "C11702") (field (name "Comment") "0402WGF1001TCE"))
      (libsource (lib "JLC_PCB") (part "0402WGF1001TCE"))
    )
    (comp (ref "RLED_3")
      (value "1k")
      (footprint "R_0402")
      (description "R - RESISTOR - SMD - 1k - 1% - 0402")
      (fields (field (name "LCSC PART #") "C11702") (field (name "Comment") "0402WGF1001TCE"))
      (libsource (lib "JLC_PCB") (part "0402WGF1001TCE"))
    )
    (comp (ref "RSCL")
      (value "10k")
      (footprint "R_0402")
      (description "R - RESISTOR - SMD - 10k - 1% - 0402")
      (fields (field (name "LCSC PART #") "C25744") (field (name "Comment") "0402WGF1002TCE"))
      (libsource (lib "JLC_PCB") (part "0402WGF1002TCE"))
    )
    (comp (ref "RSDA")
      (value "10k")
      (footprint "R_0402")
      (description "R - RESISTOR - SMD - 10k - 1% - 0402")
      (fields (field (name "LCSC PART #") "C25744") (field (name "Comment") "0402WGF1002TCE"))
      (libsource (lib "JLC_PCB") (part "0402WGF1002TCE"))
    )
    (comp (ref "RSHUNT")
      (value "100k")
      (footprint "R_0402")
      (description "R - RESISTOR - SMD - 100k - 1% -  0402")
      (fields (field (name "LCSC PART #") "C25741") (field (name "Comment") "0402WGF1003TCE"))
      (libsource (lib "JLC_PCB") (part "0402WGF1003TCE"))
    )
    (comp (ref "RSHUNT2")
      (value "100k")
      (footprint "R_0402")
      (description "R - RESISTOR - SMD - 100k - 1% -  0402")
      (fields (field (name "LCSC PART #") "C25741") (field (name "Comment") "0402WGF1003TCE"))
      (libsource (lib "JLC_PCB") (part "0402WGF1003TCE"))
    )
    (comp (ref "RSHUNT3")
      (value "100R")
      (footprint "R_0402")
      (description "R - RESISTOR - SMD - 100R - 1% - 0402")
      (fields (field (name "LCSC PART #") "C25076") (field (name "Comment") "0402WGF1000TCE"))
      (libsource (lib "JLC_PCB") (part "0402WGF1000TCE"))
    )
    (comp (ref "RSNS")
      (value "1m")
      (footprint "R_2512")
      (description "R - RESISTOR - SMD - 0.001R - 1% - 2512 - 2W")
      (fields (field (name "LCSC PART #") "C76233") (field (name "POWER") "2W"))
      (libsource (lib "JLC_PCB") (part "MRF6432(2512)LR001FTS"))
    )
    (comp (ref "RSNSN")
      (value "100R")
      (footprint "R_0402")
      (description "R - RESISTOR - SMD - 100R - 1% - 0402")
      (fields (field (name "LCSC PART #") "C25076") (field (name "Comment") "0402WGF1000TCE"))
      (libsource (lib "JLC_PCB") (part "0402WGF1000TCE"))
    )
    (comp (ref "RSNSP")
      (value "100R")
      (footprint "R_0402")
      (description "R - RESISTOR - SMD - 100R - 1% - 0402")
      (fields (field (name "LCSC PART #") "C25076") (field (name "Comment") "0402WGF1000TCE"))
      (libsource (lib "JLC_PCB") (part "0402WGF1000TCE"))
    )
    (comp (ref "RS_0")
      (value "1k")
      (footprint "R_0402")
      (description "R - RESISTOR - SMD - 1k - 1% - 0402")
      (fields (field (name "LCSC PART #") "C11702") (field (name "Comment") "0402WGF1001TCE"))
      (libsource (lib "JLC_PCB") (part "0402WGF1001TCE"))
    )
    (comp (ref "RS_1")
      (value "1k")
      (footprint "R_0402")
      (description "R - RESISTOR - SMD - 1k - 1% - 0402")
      (fields (field (name "LCSC PART #") "C11702") (field (name "Comment") "0402WGF1001TCE"))
      (libsource (lib "JLC_PCB") (part "0402WGF1001TCE"))
    )
    (comp (ref "RS_2")
      (value "1k")
      (footprint "R_0402")
      (description "R - RESISTOR - SMD - 1k - 1% - 0402")
      (fields (field (name "LCSC PART #") "C11702") (field (name "Comment") "0402WGF1001TCE"))
      (libsource (lib "JLC_PCB") (part "0402WGF1001TCE"))
    )
    (comp (ref "RS_3")
      (value "1k")
      (footprint "R_0402")
      (description "R - RESISTOR - SMD - 1k - 1% - 0402")
      (fields (field (name "LCSC PART #") "C11702") (field (name "Comment") "0402WGF1001TCE"))
      (libsource (lib "JLC_PCB") (part "0402WGF1001TCE"))
    )
    (comp (ref "RS_4")
      (value "1k")
      (footprint "R_0402")
      (description "R - RESISTOR - SMD - 1k - 1% - 0402")
      (fields (field (name "LCSC PART #") "C11702") (field (name "Comment") "0402WGF1001TCE"))
      (libsource (lib "JLC_PCB") (part "0402WGF1001TCE"))
    )
    (comp (ref "RS_5")
      (value "1k")
      (footprint "R_0402")
      (description "R - RESISTOR - SMD - 1k - 1% - 0402")
      (fields (field (name "LCSC PART #") "C11702") (field (name "Comment") "0402WGF1001TCE"))
      (libsource (lib "JLC_PCB") (part "0402WGF1001TCE"))
    )
    (comp (ref "RS_6")
      (value "1k")
      (footprint "R_0402")
      (description "R - RESISTOR - SMD - 1k - 1% - 0402")
      (fields (field (name "LCSC PART #") "C11702") (field (name "Comment") "0402WGF1001TCE"))
      (libsource (lib "JLC_PCB") (part "0402WGF1001TCE"))
    )
    (comp (ref "RS_7")
      (value "1k")
      (footprint "R_0402")
      (description "R - RESISTOR - SMD - 1k - 1% - 0402")
      (fields (field (name "LCSC PART #") "C11702") (field (name "Comment") "0402WGF1001TCE"))
      (libsource (lib "JLC_PCB") (part "0402WGF1001TCE"))
    )
    (comp (ref "RS_8")
      (value "1k")
      (footprint "R_0402")
      (description "R - RESISTOR - SMD - 1k - 1% - 0402")
      (fields (field (name "LCSC PART #") "C11702") (field (name "Comment") "0402WGF1001TCE"))
      (libsource (lib "JLC_PCB") (part "0402WGF1001TCE"))
    )
    (comp (ref "RS_9")
      (value "1k")
      (footprint "R_0402")
      (description "R - RESISTOR - SMD - 1k - 1% - 0402")
      (fields (field (name "LCSC PART #") "C11702") (field (name "Comment") "0402WGF1001TCE"))
      (libsource (lib "JLC_PCB") (part "0402WGF1001TCE"))
    )
    (comp (ref "RS_10")
      (value "1k")
      (footprint "R_0402")
      (description "R - RESISTOR - SMD - 1k - 1% - 0402")
      (fields (field (name "LCSC PART #") "C11702") (field (name "Comment") "0402WGF1001TCE"))
      (libsource (lib "JLC_PCB") (part "0402WGF1001TCE"))
    )
    (comp (ref "RS_11")
      (value "1k")
      (footprint "R_0402")
      (description "R - RESISTOR - SMD - 1k - 1% - 0402")
      (fields (field (name "LCSC PART #") "C11702") (field (name "Comment") "0402WGF1001TCE"))
      (libsource (lib "JLC_PCB") (part "0402WGF1001TCE"))
    )
    (comp (ref "RS_12")
      (value "1k")
      (footprint "R_0402")
      (description "R - RESISTOR - SMD - 1k - 1% - 0402")
      (fields (field (name "LCSC PART #") "C11702") (field (name "Comment") "0402WGF1001TCE"))
      (libsource (lib "JLC_PCB") (part "0402WGF1001TCE"))
    )
    (comp (ref "RS_13")
      (value "1k")
      (footprint "R_0402")
      (description "R - RESISTOR - SMD - 1k - 1% - 0402")
      (fields (field (name "LCSC PART #") "C11702") (field (name "Comment") "0402WGF1001TCE"))
      (libsource (lib "JLC_PCB") (part "0402WGF1001TCE"))
    )
    (comp (ref "RS_14")
      (value "1k")
      (footprint "R_0402")
      (description "R - RESISTOR - SMD - 1k - 1% - 0402")
      (fields (field (name "LCSC PART #") "C11702") (field (name "Comment") "0402WGF1001TCE"))
      (libsource (lib "JLC_PCB") (part "0402WGF1001TCE"))
    )
    (comp (ref "RS_15")
      (value "1k")
      (footprint "R_0402")
      (description "R - RESISTOR - SMD - 1k - 1% - 0402")
      (fields (field (name "LCSC PART #") "C11702") (field (name "Comment") "0402WGF1001TCE"))
      (libsource (lib "JLC_PCB") (part "0402WGF1001TCE"))
    )
    (comp (ref "RS_16")
      (value "1k")
      (footprint "R_0402")
      (description "R - RESISTOR - SMD - 1k - 1% - 0402")
      (fields (field (name "LCSC PART #") "C11702") (field (name "Comment") "0402WGF1001TCE"))
      (libsource (lib "JLC_PCB") (part "0402WGF1001TCE"))
    )
    (comp (ref "RS_17")
      (value "1k")
      (footprint "R_0402")
      (description "R - RESISTOR - SMD - 1k - 1% - 0402")
      (fields (field (name "LCSC PART #") "C11702") (field (name "Comment") "0402WGF1001TCE"))
      (libsource (lib "JLC_PCB") (part "0402WGF1001TCE"))
    )
    (comp (ref "RS_18")
      (value "1k")
      (footprint "R_0402")
      (description "R - RESISTOR - SMD - 1k - 1% - 0402")
      (fields (field (name "LCSC PART #") "C11702") (field (name "Comment") "0402WGF1001TCE"))
      (libsource (lib "JLC_PCB") (part "0402WGF1001TCE"))
    )
    (comp (ref "RS_19")
      (value "1k")
      (footprint "R_0402")
      (description "R - RESISTOR - SMD - 1k - 1% - 0402")
      (fields (field (name "LCSC PART #") "C11702") (field (name "Comment") "0402WGF1001TCE"))
      (libsource (lib "JLC_PCB") (part "0402WGF1001TCE"))
    )
    (comp (ref "RS_20")
      (value "1k")
      (footprint "R_0402")
      (description "R - RESISTOR - SMD - 1k - 1% - 0402")
      (fields (field (name "LCSC PART #") "C11702") (field (name "Comment") "0402WGF1001TCE"))
      (libsource (lib "JLC_PCB") (part "0402WGF1001TCE"))
    )
    (comp (ref "RS_21")
      (value "1k")
      (footprint "R_0402")
      (description "R - RESISTOR - SMD - 1k - 1% - 0402")
      (fields (field (name "LCSC PART #") "C11702") (field (name "Comment") "0402WGF1001TCE"))
      (libsource (lib "JLC_PCB") (part "0402WGF1001TCE"))
    )
    (comp (ref "RS_22")
      (value "1k")
      (footprint "R_0402")
      (description "R - RESISTOR - SMD - 1k - 1% - 0402")
      (fields (field (name "LCSC PART #") "C11702") (field (name "Comment") "0402WGF1001TCE"))
      (libsource (lib "JLC_PCB") (part "0402WGF1001TCE"))
    )
    (comp (ref "RS_23")
      (value "1k")
      (footprint "R_0402")
      (description "R - RESISTOR - SMD - 1k - 1% - 0402")
      (fields (field (name "LCSC PART #") "C11702") (field (name "Comment") "0402WGF1001TCE"))
      (libsource (lib "JLC_PCB") (part "0402WGF1001TCE"))
    )
    (comp (ref "RS_24")
      (value "1k")
      (footprint "R_0402")
      (description "R - RESISTOR - SMD - 1k - 1% - 0402")
      (fields (field (name "LCSC PART #") "C11702") (field (name "Comment") "0402WGF1001TCE"))
      (libsource (lib "JLC_PCB") (part "0402WGF1001TCE"))
    )
    (comp (ref "RS_25")
      (value "1k")
      (footprint "R_0402")
      (description "R - RESISTOR - SMD - 1k - 1% - 0402")
      (fields (field (name "LCSC PART #") "C11702") (field (name "Comment") "0402WGF1001TCE"))
      (libsource (lib "JLC_PCB") (part "0402WGF1001TCE"))
    )
    (comp (ref "RS_26")
      (value "1k")
      (footprint "R_0402")
      (description "R - RESISTOR - SMD - 1k - 1% - 0402")
      (fields (field (name "LCSC PART #") "C11702") (field (name "Comment") "0402WGF1001TCE"))
      (libsource (lib "JLC_PCB") (part "0402WGF1001TCE"))
    )
    (comp (ref "RS_27")
      (value "1k")
      (footprint "R_0402")
      (description "R - RESISTOR - SMD - 1k - 1% - 0402")
      (fields (field (name "LCSC PART #") "C11702") (field (name "Comment") "0402WGF1001TCE"))
      (libsource (lib "JLC_PCB") (part "0402WGF1001TCE"))
    )
    (comp (ref "RS_28")
      (value "1k")
      (footprint "R_0402")
      (description "R - RESISTOR - SMD - 1k - 1% - 0402")
      (fields (field (name "LCSC PART #") "C11702") (field (name "Comment") "0402WGF1001TCE"))
      (libsource (lib "JLC_PCB") (part "0402WGF1001TCE"))
    )
    (comp (ref "RS_29")
      (value "1k")
      (footprint "R_0402")
      (description "R - RESISTOR - SMD - 1k - 1% - 0402")
      (fields (field (name "LCSC PART #") "C11702") (field (name "Comment") "0402WGF1001TCE"))
      (libsource (lib "JLC_PCB") (part "0402WGF1001TCE"))
    )
    (comp (ref "RTS2")
      (value "10k")
      (footprint "R_0402")
      (description "RT - NTC THERMISTOR - 10k - 1% - 0402")
      (fields (field (name "LCSC PART #") "C77131") (field (name "Comment") "NCP15XH103F03RC"))
      (libsource (lib "JLC_PCB") (part "NCP15XH103F03RC"))
    )
    (comp (ref "RT_0B")
      (value "10k")
      (footprint "R_0402")
      (description "R - RESISTOR - SMD - 10k - 1% - 0402")
      (fields (field (name "LCSC PART #") "C25744") (field (name "Comment") "0402WGF1002TCE"))
      (libsource (lib "JLC_PCB") (part "0402WGF1002TCE"))
    )
    (comp (ref "RT_1B")
      (value "10k")
      (footprint "R_0402")
      (description "R - RESISTOR - SMD - 10k - 1% - 0402")
      (fields (field (name "LCSC PART #") "C25744") (field (name "Comment") "0402WGF1002TCE"))
      (libsource (lib "JLC_PCB") (part "0402WGF1002TCE"))
    )
    (comp (ref "RT_2B")
      (value "10k")
      (footprint "R_0402")
      (description "R - RESISTOR - SMD - 10k - 1% - 0402")
      (fields (field (name "LCSC PART #") "C25744") (field (name "Comment") "0402WGF1002TCE"))
      (libsource (lib "JLC_PCB") (part "0402WGF1002TCE"))
    )
    (comp (ref "RT_3B")
      (value "10k")
      (footprint "R_0402")
      (description "R - RESISTOR - SMD - 10k - 1% - 0402")
      (fields (field (name "LCSC PART #") "C25744") (field (name "Comment") "0402WGF1002TCE"))
      (libsource (lib "JLC_PCB") (part "0402WGF1002TCE"))
    )
    (comp (ref "RT_4B")
      (value "10k")
      (footprint "R_0402")
      (description "R - RESISTOR - SMD - 10k - 1% - 0402")
      (fields (field (name "LCSC PART #") "C25744") (field (name "Comment") "0402WGF1002TCE"))
      (libsource (lib "JLC_PCB") (part "0402WGF1002TCE"))
    )
    (comp (ref "RT_5B")
      (value "10k")
      (footprint "R_0402")
      (description "R - RESISTOR - SMD - 10k - 1% - 0402")
      (fields (field (name "LCSC PART #") "C25744") (field (name "Comment") "0402WGF1002TCE"))
      (libsource (lib "JLC_PCB") (part "0402WGF1002TCE"))
    )
    (comp (ref "RT_6B")
      (value "10k")
      (footprint "R_0402")
      (description "R - RESISTOR - SMD - 10k - 1% - 0402")
      (fields (field (name "LCSC PART #") "C25744") (field (name "Comment") "0402WGF1002TCE"))
      (libsource (lib "JLC_PCB") (part "0402WGF1002TCE"))
    )
    (comp (ref "RT_7B")
      (value "10k")
      (footprint "R_0402")
      (description "R - RESISTOR - SMD - 10k - 1% - 0402")
      (fields (field (name "LCSC PART #") "C25744") (field (name "Comment") "0402WGF1002TCE"))
      (libsource (lib "JLC_PCB") (part "0402WGF1002TCE"))
    )
    (comp (ref "RT_8B")
      (value "10k")
      (footprint "R_0402")
      (description "R - RESISTOR - SMD - 10k - 1% - 0402")
      (fields (field (name "LCSC PART #") "C25744") (field (name "Comment") "0402WGF1002TCE"))
      (libsource (lib "JLC_PCB") (part "0402WGF1002TCE"))
    )
    (comp (ref "RT_9B")
      (value "10k")
      (footprint "R_0402")
      (description "R - RESISTOR - SMD - 10k - 1% - 0402")
      (fields (field (name "LCSC PART #") "C25744") (field (name "Comment") "0402WGF1002TCE"))
      (libsource (lib "JLC_PCB") (part "0402WGF1002TCE"))
    )
    (comp (ref "RT_10B")
      (value "10k")
      (footprint "R_0402")
      (description "R - RESISTOR - SMD - 10k - 1% - 0402")
      (fields (field (name "LCSC PART #") "C25744") (field (name "Comment") "0402WGF1002TCE"))
      (libsource (lib "JLC_PCB") (part "0402WGF1002TCE"))
    )
    (comp (ref "RT_11B")
      (value "10k")
      (footprint "R_0402")
      (description "R - RESISTOR - SMD - 10k - 1% - 0402")
      (fields (field (name "LCSC PART #") "C25744") (field (name "Comment") "0402WGF1002TCE"))
      (libsource (lib "JLC_PCB") (part "0402WGF1002TCE"))
    )
    (comp (ref "RT_12B")
      (value "10k")
      (footprint "R_0402")
      (description "R - RESISTOR - SMD - 10k - 1% - 0402")
      (fields (field (name "LCSC PART #") "C25744") (field (name "Comment") "0402WGF1002TCE"))
      (libsource (lib "JLC_PCB") (part "0402WGF1002TCE"))
    )
    (comp (ref "RT_13B")
      (value "10k")
      (footprint "R_0402")
      (description "R - RESISTOR - SMD - 10k - 1% - 0402")
      (fields (field (name "LCSC PART #") "C25744") (field (name "Comment") "0402WGF1002TCE"))
      (libsource (lib "JLC_PCB") (part "0402WGF1002TCE"))
    )
    (comp (ref "RT_14B")
      (value "10k")
      (footprint "R_0402")
      (description "R - RESISTOR - SMD - 10k - 1% - 0402")
      (fields (field (name "LCSC PART #") "C25744") (field (name "Comment") "0402WGF1002TCE"))
      (libsource (lib "JLC_PCB") (part "0402WGF1002TCE"))
    )
    (comp (ref "RT_15B")
      (value "10k")
      (footprint "R_0402")
      (description "R - RESISTOR - SMD - 10k - 1% - 0402")
      (fields (field (name "LCSC PART #") "C25744") (field (name "Comment") "0402WGF1002TCE"))
      (libsource (lib "JLC_PCB") (part "0402WGF1002TCE"))
    )
    (comp (ref "R_Q18G")
      (value "10k")
      (footprint "R_0402")
      (description "R - RESISTOR - SMD - 10k - 1% - 0402")
      (fields (field (name "LCSC PART #") "C25744") (field (name "Comment") "0402WGF1002TCE"))
      (libsource (lib "JLC_PCB") (part "0402WGF1002TCE"))
    )
    (comp (ref "R_STBY1")
      (value "10k")
      (footprint "R_0402")
      (description "R - RESISTOR - SMD - 10k - 1% - 0402")
      (fields (field (name "LCSC PART #") "C25744") (field (name "Comment") "0402WGF1002TCE"))
      (libsource (lib "JLC_PCB") (part "0402WGF1002TCE"))
    )
    (comp (ref "R_STBY2")
      (value "10k")
      (footprint "R_0402")
      (description "R - RESISTOR - SMD - 10k - 1% - 0402")
      (fields (field (name "LCSC PART #") "C25744") (field (name "Comment") "0402WGF1002TCE"))
      (libsource (lib "JLC_PCB") (part "0402WGF1002TCE"))
    )
    (comp (ref "R_VBUS1")
      (value "10k")
      (footprint "R_0402")
      (description "R - RESISTOR - SMD - 10k - 1% - 0402")
      (fields (field (name "LCSC PART #") "C25744") (field (name "Comment") "0402WGF1002TCE"))
      (libsource (lib "JLC_PCB") (part "0402WGF1002TCE"))
    )
    (comp (ref "R_VBUS2")
      (value "10k")
      (footprint "R_0402")
      (description "R - RESISTOR - SMD - 10k - 1% - 0402")
      (fields (field (name "LCSC PART #") "C25744") (field (name "Comment") "0402WGF1002TCE"))
      (libsource (lib "JLC_PCB") (part "0402WGF1002TCE"))
    )
    (comp (ref "R_VBUS3")
      (value "1k")
      (footprint "R_0402")
      (description "R - RESISTOR - SMD - 1k - 1% - 0402")
      (fields (field (name "LCSC PART #") "C11702") (field (name "Comment") "0402WGF1001TCE"))
      (libsource (lib "JLC_PCB") (part "0402WGF1001TCE"))
    )
    (comp (ref "R_WK")
      (value "100R")
      (footprint "R_0402")
      (description "R - RESISTOR - SMD - 100R - 1% - 0402")
      (fields (field (name "LCSC PART #") "C25076") (field (name "Comment") "0402WGF1000TCE"))
      (libsource (lib "JLC_PCB") (part "0402WGF1000TCE"))
    )
    (comp (ref "SW1")
      (value "TS-1187A-C-C-B")
      (footprint "TS-1187A-C-C-B")
      (description "SW - SWITCH - SPST - NO - Top Actuated Surface Mount")
      (fields (field (name "LCSC PART #") "C318889"))
      (libsource (lib "JLC_PCB") (part "TS-1187A-C-C-B"))
    )
    (comp (ref "SW_WAKE")
      (value "TS-1187A-C-C-B")
      (footprint "TS-1187A-C-C-B")
      (description "SW - SWITCH - SPST - NO - Top Actuated Surface Mount")
      (fields (field (name "LCSC PART #") "C318889"))
      (libsource (lib "JLC_PCB") (part "TS-1187A-C-C-B"))
    )
    (comp (ref "TSQ1a")
      (value "2N7002")
      (footprint "TO-236AB")
      (description "Q - TRANSISTOR - MOSFET (N) - 60V - 200mW")
      (fields (field (name "LCSC PART #") "C8545"))
      (libsource (lib "JLC_PCB") (part "2N7002"))
    )
    (comp (ref "TSQ1b")
      (value "2N7002")
      (footprint "TO-236AB")
      (description "Q - TRANSISTOR - MOSFET (N) - 60V - 200mW")
      (fields (field (name "LCSC PART #") "C8545"))
      (libsource (lib "JLC_PCB") (part "2N7002"))
    )
    (comp (ref "TS_C1_A")
      (value "10k")
      (footprint "R_0402")
      (description "RT - NTC THERMISTOR - 10k - 1% - 0402")
      (fields (field (name "LCSC PART #") "C77131") (field (name "Comment") "NCP15XH103F03RC"))
      (libsource (lib "JLC_PCB") (part "NCP15XH103F03RC"))
    )
    (comp (ref "TS_C1_B")
      (value "10k")
      (footprint "R_0402")
      (description "RT - NTC THERMISTOR - 10k - 1% - 0402")
      (fields (field (name "LCSC PART #") "C77131") (field (name "Comment") "NCP15XH103F03RC"))
      (libsource (lib "JLC_PCB") (part "NCP15XH103F03RC"))
    )
    (comp (ref "TS_C2_A")
      (value "10k")
      (footprint "R_0402")
      (description "RT - NTC THERMISTOR - 10k - 1% - 0402")
      (fields (field (name "LCSC PART #") "C77131") (field (name "Comment") "NCP15XH103F03RC"))
      (libsource (lib "JLC_PCB") (part "NCP15XH103F03RC"))
    )
    (comp (ref "TS_C2_B")
      (value "10k")
      (footprint "R_0402")
      (description "RT - NTC THERMISTOR - 10k - 1% - 0402")
      (fields (field (name "LCSC PART #") "C77131") (field (name "Comment") "NCP15XH103F03RC"))
      (libsource (lib "JLC_PCB") (part "NCP15XH103F03RC"))
    )
    (comp (ref "TS_C3_A")
      (value "10k")
      (footprint "R_0402")
      (description "RT - NTC THERMISTOR - 10k - 1% - 0402")
      (fields (field (name "LCSC PART #") "C77131") (field (name "Comment") "NCP15XH103F03RC"))
      (libsource (lib "JLC_PCB") (part "NCP15XH103F03RC"))
    )
    (comp (ref "TS_C3_B")
      (value "10k")
      (footprint "R_0402")
      (description "RT - NTC THERMISTOR - 10k - 1% - 0402")
      (fields (field (name "LCSC PART #") "C77131") (field (name "Comment") "NCP15XH103F03RC"))
      (libsource (lib "JLC_PCB") (part "NCP15XH103F03RC"))
    )
    (comp (ref "TS_C4_A")
      (value "10k")
      (footprint "R_0402")
      (description "RT - NTC THERMISTOR - 10k - 1% - 0402")
      (fields (field (name "LCSC PART #") "C77131") (field (name "Comment") "NCP15XH103F03RC"))
      (libsource (lib "JLC_PCB") (part "NCP15XH103F03RC"))
    )
    (comp (ref "TS_C4_B")
      (value "10k")
      (footprint "R_0402")
      (description "RT - NTC THERMISTOR - 10k - 1% - 0402")
      (fields (field (name "LCSC PART #") "C77131") (field (name "Comment") "NCP15XH103F03RC"))
      (libsource (lib "JLC_PCB") (part "NCP15XH103F03RC"))
    )
    (comp (ref "TS_C5_A")
      (value "10k")
      (footprint "R_0402")
      (description "RT - NTC THERMISTOR - 10k - 1% - 0402")
      (fields (field (name "LCSC PART #") "C77131") (field (name "Comment") "NCP15XH103F03RC"))
      (libsource (lib "JLC_PCB") (part "NCP15XH103F03RC"))
    )
    (comp (ref "TS_C5_B")
      (value "10k")
      (footprint "R_0402")
      (description "RT - NTC THERMISTOR - 10k - 1% - 0402")
      (fields (field (name "LCSC PART #") "C77131") (field (name "Comment") "NCP15XH103F03RC"))
      (libsource (lib "JLC_PCB") (part "NCP15XH103F03RC"))
    )
    (comp (ref "TS_C6_A")
      (value "10k")
      (footprint "R_0402")
      (description "RT - NTC THERMISTOR - 10k - 1% - 0402")
      (fields (field (name "LCSC PART #") "C77131") (field (name "Comment") "NCP15XH103F03RC"))
      (libsource (lib "JLC_PCB") (part "NCP15XH103F03RC"))
    )
    (comp (ref "TS_C6_B")
      (value "10k")
      (footprint "R_0402")
      (description "RT - NTC THERMISTOR - 10k - 1% - 0402")
      (fields (field (name "LCSC PART #") "C77131") (field (name "Comment") "NCP15XH103F03RC"))
      (libsource (lib "JLC_PCB") (part "NCP15XH103F03RC"))
    )
    (comp (ref "TS_C7_A")
      (value "10k")
      (footprint "R_0402")
      (description "RT - NTC THERMISTOR - 10k - 1% - 0402")
      (fields (field (name "LCSC PART #") "C77131") (field (name "Comment") "NCP15XH103F03RC"))
      (libsource (lib "JLC_PCB") (part "NCP15XH103F03RC"))
    )
    (comp (ref "TS_C7_B")
      (value "10k")
      (footprint "R_0402")
      (description "RT - NTC THERMISTOR - 10k - 1% - 0402")
      (fields (field (name "LCSC PART #") "C77131") (field (name "Comment") "NCP15XH103F03RC"))
      (libsource (lib "JLC_PCB") (part "NCP15XH103F03RC"))
    )
    (comp (ref "TS_C8_A")
      (value "10k")
      (footprint "R_0402")
      (description "RT - NTC THERMISTOR - 10k - 1% - 0402")
      (fields (field (name "LCSC PART #") "C77131") (field (name "Comment") "NCP15XH103F03RC"))
      (libsource (lib "JLC_PCB") (part "NCP15XH103F03RC"))
    )
    (comp (ref "TS_C8_B")
      (value "10k")
      (footprint "R_0402")
      (description "RT - NTC THERMISTOR - 10k - 1% - 0402")
      (fields (field (name "LCSC PART #") "C77131") (field (name "Comment") "NCP15XH103F03RC"))
      (libsource (lib "JLC_PCB") (part "NCP15XH103F03RC"))
    )
    (comp (ref "TS_C9_A")
      (value "10k")
      (footprint "R_0402")
      (description "RT - NTC THERMISTOR - 10k - 1% - 0402")
      (fields (field (name "LCSC PART #") "C77131") (field (name "Comment") "NCP15XH103F03RC"))
      (libsource (lib "JLC_PCB") (part "NCP15XH103F03RC"))
    )
    (comp (ref "TS_C9_B")
      (value "10k")
      (footprint "R_0402")
      (description "RT - NTC THERMISTOR - 10k - 1% - 0402")
      (fields (field (name "LCSC PART #") "C77131") (field (name "Comment") "NCP15XH103F03RC"))
      (libsource (lib "JLC_PCB") (part "NCP15XH103F03RC"))
    )
    (comp (ref "TS_C10_A")
      (value "10k")
      (footprint "R_0402")
      (description "RT - NTC THERMISTOR - 10k - 1% - 0402")
      (fields (field (name "LCSC PART #") "C77131") (field (name "Comment") "NCP15XH103F03RC"))
      (libsource (lib "JLC_PCB") (part "NCP15XH103F03RC"))
    )
    (comp (ref "TS_C10_B")
      (value "10k")
      (footprint "R_0402")
      (description "RT - NTC THERMISTOR - 10k - 1% - 0402")
      (fields (field (name "LCSC PART #") "C77131") (field (name "Comment") "NCP15XH103F03RC"))
      (libsource (lib "JLC_PCB") (part "NCP15XH103F03RC"))
    )
    (comp (ref "TS_C11_A")
      (value "10k")
      (footprint "R_0402")
      (description "RT - NTC THERMISTOR - 10k - 1% - 0402")
      (fields (field (name "LCSC PART #") "C77131") (field (name "Comment") "NCP15XH103F03RC"))
      (libsource (lib "JLC_PCB") (part "NCP15XH103F03RC"))
    )
    (comp (ref "TS_C11_B")
      (value "10k")
      (footprint "R_0402")
      (description "RT - NTC THERMISTOR - 10k - 1% - 0402")
      (fields (field (name "LCSC PART #") "C77131") (field (name "Comment") "NCP15XH103F03RC"))
      (libsource (lib "JLC_PCB") (part "NCP15XH103F03RC"))
    )
    (comp (ref "TS_C12_A")
      (value "10k")
      (footprint "R_0402")
      (description "RT - NTC THERMISTOR - 10k - 1% - 0402")
      (fields (field (name "LCSC PART #") "C77131") (field (name "Comment") "NCP15XH103F03RC"))
      (libsource (lib "JLC_PCB") (part "NCP15XH103F03RC"))
    )
    (comp (ref "TS_C12_B")
      (value "10k")
      (footprint "R_0402")
      (description "RT - NTC THERMISTOR - 10k - 1% - 0402")
      (fields (field (name "LCSC PART #") "C77131") (field (name "Comment") "NCP15XH103F03RC"))
      (libsource (lib "JLC_PCB") (part "NCP15XH103F03RC"))
    )
    (comp (ref "TS_C13A")
      (value "10k")
      (footprint "R_0402")
      (description "RT - NTC THERMISTOR - 10k - 1% - 0402")
      (fields (field (name "LCSC PART #") "C77131") (field (name "Comment") "NCP15XH103F03RC"))
      (libsource (lib "JLC_PCB") (part "NCP15XH103F03RC"))
    )
    (comp (ref "TS_C13_B")
      (value "10k")
      (footprint "R_0402")
      (description "RT - NTC THERMISTOR - 10k - 1% - 0402")
      (fields (field (name "LCSC PART #") "C77131") (field (name "Comment") "NCP15XH103F03RC"))
      (libsource (lib "JLC_PCB") (part "NCP15XH103F03RC"))
    )
    (comp (ref "TS_C14_A")
      (value "10k")
      (footprint "R_0402")
      (description "RT - NTC THERMISTOR - 10k - 1% - 0402")
      (fields (field (name "LCSC PART #") "C77131") (field (name "Comment") "NCP15XH103F03RC"))
      (libsource (lib "JLC_PCB") (part "NCP15XH103F03RC"))
    )
    (comp (ref "TS_C14_B")
      (value "10k")
      (footprint "R_0402")
      (description "RT - NTC THERMISTOR - 10k - 1% - 0402")
      (fields (field (name "LCSC PART #") "C77131") (field (name "Comment") "NCP15XH103F03RC"))
      (libsource (lib "JLC_PCB") (part "NCP15XH103F03RC"))
    )
    (comp (ref "U1")
      (value "BQ7694002DBTR")
      (footprint "TSSOP50P580X150-44N")
      (description "9 to 15-series cell li-ion and li-phosphate battery monitor (bq76940 family)")
      (libsource (lib "U") (part "BQ7694002DBTR"))
    )
    (comp (ref "U2")
      (value "74HC4067PW,118")
      (footprint "SILICON:TSSOP-24-P0.65MM-W4.4MM")
      (description "U - IC -16 Port Analog MUX")
      (fields (field (name "LCSC PART #") "C179326"))
      (libsource (lib "JLC_PCB") (part "74HC4067PW,118"))
    )
    (comp (ref "U100")
      (value "GD32F103CBT6")
      (footprint "SILICON:QFP-48-P0.5MM")
      (description "U - IC - MCU, 128 KB Flash, 20 KB Internal RAM, 37 I/Os, 48-pin LQFP, -40 to 85 degC")
      (fields (field (name "LCSC PART #") "C77979"))
      (libsource (lib "JLC_PCB") (part "GD32F103CBT6"))
    )
    (comp (ref "U101")
      (value "XC6206P332MR")
      (footprint "SILICON:TO-236AB")
      (description "U - IC - LDO 3.3V 200mA")
      (fields (field (name "LCSC PART #") "C5446"))
      (libsource (lib "JLC_PCB") (part "XC6206P332MR"))
    )
    (comp (ref "Y100")
      (value "X50328MSB2GI")
      (footprint "YSX530GA")
      (description "Y - RESONATOR - 8MHZ ±10PPM - SMD-5032")
      (fields (field (name "ALTIUM_VALUE") "8MHz") (field (name "LCSC PART #") "C115962"))
      (libsource (lib "JLC_PCB") (part "X50328MSB2GI"))
    )
  )
  (nets
    (net (code "1") (name "/3V3_EN") (class "Default")
      (node (ref "3V3R2") (pin "2") (pinfunction "2_2") (pintype "passive"))
      (node (ref "U100") (pin "3") (pinfunction "PC14-OSC32_IN_3") (pintype "bidirectional"))
    )
    (net (code "2") (name "/ADDRESS_SENSE_EN") (class "Default")
      (node (ref "D_ADR_VCC") (pin "2") (pinfunction "A_2") (pintype "passive"))
      (node (ref "U100") (pin "38") (pinfunction "PA15_38") (pintype "bidirectional"))
    )
    (net (code "3") (name "/AFE_ALERT") (class "Default")
      (node (ref "U1") (pin "44") (pinfunction "ALERT_44") (pintype "passive"))
      (node (ref "U100") (pin "2") (pinfunction "PC13-TAMPER-RTC_2") (pintype "bidirectional"))
    )
    (net (code "4") (name "/AFE_SCL") (class "Default")
      (node (ref "RSCL") (pin "2") (pinfunction "2_2") (pintype "passive"))
      (node (ref "U1") (pin "5") (pinfunction "SCL_5") (pintype "passive"))
      (node (ref "U100") (pin "21") (pinfunction "PB10_21") (pintype "bidirectional"))
    )
    (net (code "5") (name "/AFE_SDA") (class "Default")
      (node (ref "RSDA") (pin "2") (pinfunction "2_2") (pintype "passive"))
      (node (ref "U1") (pin "4") (pinfunction "SDA_4") (pintype "passive"))
      (node (ref "U100") (pin "22") (pinfunction "PB11_22") (pintype "bidirectional"))
    )
    (net (code "6") (name "/AFE_WAKE") (class "Default")
      (node (ref "U1") (pin "6") (pinfunction "TS1_6") (pintype "passive"))
      (node (ref "U100") (pin "26") (pinfunction "PB13_26") (pintype "bidirectional"))
    )
    (net (code "7") (name "/A_GND") (class "Default")
      (node (ref "C105") (pin "1") (pinfunction "1_1") (pintype "passive"))
      (node (ref "CTS_15") (pin "1") (pinfunction "1_1") (pintype "passive"))
      (node (ref "NT_1") (pin "1") (pinfunction "1_1") (pintype "passive"))
      (node (ref "R102") (pin "2") (pinfunction "2_2") (pintype "passive"))
      (node (ref "RTS2") (pin "1") (pinfunction "1_1") (pintype "passive"))
      (node (ref "TSQ1a") (pin "2") (pinfunction "S_2") (pintype "passive"))
      (node (ref "TSQ1b") (pin "2") (pinfunction "S_2") (pintype "passive"))
      (node (ref "U100") (pin "8") (pinfunction "VSSA_8") (pintype "power_in"))
    )
    (net (code "8") (name "/BATT_EN") (class "Default")
      (node (ref "QBEN") (pin "1") (pinfunction "G_1") (pintype "passive"))
      (node (ref "QBENR") (pin "1") (pinfunction "1_1") (pintype "passive"))
      (node (ref "U100") (pin "14") (pinfunction "PA4_14") (pintype "bidirectional"))
    )
    (net (code "9") (name "/B_SCL") (class "Default")
      (node (ref "U100") (pin "42") (pinfunction "PB6_42") (pintype "bidirectional"))
    )
    (net (code "10") (name "/B_SDA") (class "Default")
      (node (ref "U100") (pin "43") (pinfunction "PB7_43") (pintype "bidirectional"))
    )
    (net (code "11") (name "/C0") (class "Default")
      (node (ref "CC0A") (pin "1") (pinfunction "1_1") (pintype "passive"))
      (node (ref "NT_C0") (pin "1") (pinfunction "1_1") (pintype "passive"))
      (node (ref "RC0") (pin "2") (pinfunction "2_2") (pintype "passive"))
    )
    (net (code "12") (name "/C1") (class "Default")
      (node (ref "CC0B") (pin "2") (pinfunction "2_2") (pintype "passive"))
      (node (ref "CC1") (pin "1") (pinfunction "1_1") (pintype "passive"))
      (node (ref "NT_C1") (pin "2") (pinfunction "2_2") (pintype "passive"))
      (node (ref "RC1") (pin "2") (pinfunction "2_2") (pintype "passive"))
    )
    (net (code "13") (name "/C2") (class "Default")
      (node (ref "CC1") (pin "2") (pinfunction "2_2") (pintype "passive"))
      (node (ref "CC2") (pin "1") (pinfunction "1_1") (pintype "passive"))
      (node (ref "NT_C2") (pin "1") (pinfunction "1_1") (pintype "passive"))
      (node (ref "RC2") (pin "2") (pinfunction "2_2") (pintype "passive"))
    )
    (net (code "14") (name "/C3") (class "Default")
      (node (ref "CC2") (pin "2") (pinfunction "2_2") (pintype "passive"))
      (node (ref "CC3") (pin "1") (pinfunction "1_1") (pintype "passive"))
      (node (ref "NT_C3") (pin "2") (pinfunction "2_2") (pintype "passive"))
      (node (ref "RC3") (pin "2") (pinfunction "2_2") (pintype "passive"))
    )
    (net (code "15") (name "/C4") (class "Default")
      (node (ref "CC3") (pin "2") (pinfunction "2_2") (pintype "passive"))
      (node (ref "CC4") (pin "1") (pinfunction "1_1") (pintype "passive"))
      (node (ref "NT_C4") (pin "1") (pinfunction "1_1") (pintype "passive"))
      (node (ref "RC4") (pin "2") (pinfunction "2_2") (pintype "passive"))
    )
    (net (code "16") (name "/C5") (class "Default")
      (node (ref "CC4") (pin "2") (pinfunction "2_2") (pintype "passive"))
      (node (ref "CC5A") (pin "1") (pinfunction "1_1") (pintype "passive"))
      (node (ref "NT_C5") (pin "2") (pinfunction "2_2") (pintype "passive"))
      (node (ref "RC5A") (pin "2") (pinfunction "2_2") (pintype "passive"))
      (node (ref "RC5B") (pin "2") (pinfunction "2_2") (pintype "passive"))
    )
    (net (code "17") (name "/C6") (class "Default")
      (node (ref "CC5B") (pin "2") (pinfunction "2_2") (pintype "passive"))
      (node (ref "CC6") (pin "1") (pinfunction "1_1") (pintype "passive"))
      (node (ref "NT_C6") (pin "1") (pinfunction "1_1") (pintype "passive"))
      (node (ref "RC6") (pin "2") (pinfunction "2_2") (pintype "passive"))
    )
    (net (code "18") (name "/C7") (class "Default")
      (node (ref "CC6") (pin "2") (pinfunction "2_2") (pintype "passive"))
      (node (ref "CC7") (pin "1") (pinfunction "1_1") (pintype "passive"))
      (node (ref "NT_C7") (pin "2") (pinfunction "2_2") (pintype "passive"))
      (node (ref "RC7") (pin "2") (pinfunction "2_2") (pintype "passive"))
    )
    (net (code "19") (name "/C8") (class "Default")
      (node (ref "CC7") (pin "2") (pinfunction "2_2") (pintype "passive"))
      (node (ref "CC8") (pin "1") (pinfunction "1_1") (pintype "passive"))
      (node (ref "NT_C8") (pin "1") (pinfunction "1_1") (pintype "passive"))
      (node (ref "RC8") (pin "2") (pinfunction "2_2") (pintype "passive"))
    )
    (net (code "20") (name "/C9") (class "Default")
      (node (ref "CC8") (pin "2") (pinfunction "2_2") (pintype "passive"))
      (node (ref "CC9") (pin "1") (pinfunction "1_1") (pintype "passive"))
      (node (ref "NT_C9") (pin "2") (pinfunction "2_2") (pintype "passive"))
      (node (ref "RC9") (pin "2") (pinfunction "2_2") (pintype "passive"))
    )
    (net (code "21") (name "/C10") (class "Default")
      (node (ref "CC10A") (pin "1") (pinfunction "1_1") (pintype "passive"))
      (node (ref "CC9") (pin "2") (pinfunction "2_2") (pintype "passive"))
      (node (ref "NT_C10") (pin "1") (pinfunction "1_1") (pintype "passive"))
      (node (ref "RC10A") (pin "2") (pinfunction "2_2") (pintype "passive"))
      (node (ref "RC10B") (pin "2") (pinfunction "2_2") (pintype "passive"))
    )
    (net (code "22") (name "/C11") (class "Default")
      (node (ref "CC10B") (pin "2") (pinfunction "2_2") (pintype "passive"))
      (node (ref "CC11") (pin "1") (pinfunction "1_1") (pintype "passive"))
      (node (ref "NT_C11") (pin "2") (pinfunction "2_2") (pintype "passive"))
      (node (ref "RC11") (pin "2") (pinfunction "2_2") (pintype "passive"))
    )
    (net (code "23") (name "/C12") (class "Default")
      (node (ref "CC11") (pin "2") (pinfunction "2_2") (pintype "passive"))
      (node (ref "CC12") (pin "1") (pinfunction "1_1") (pintype "passive"))
      (node (ref "NT_C12") (pin "1") (pinfunction "1_1") (pintype "passive"))
      (node (ref "RC12") (pin "2") (pinfunction "2_2") (pintype "passive"))
    )
    (net (code "24") (name "/C13") (class "Default")
      (node (ref "CC12") (pin "2") (pinfunction "2_2") (pintype "passive"))
      (node (ref "CC13") (pin "1") (pinfunction "1_1") (pintype "passive"))
      (node (ref "NT_C13") (pin "2") (pinfunction "2_2") (pintype "passive"))
      (node (ref "NT_CSHORT") (pin "2") (pinfunction "2_2") (pintype "passive"))
      (node (ref "RC13") (pin "2") (pinfunction "2_2") (pintype "passive"))
    )
    (net (code "25") (name "/C14") (class "Default")
      (node (ref "CC13") (pin "2") (pinfunction "2_2") (pintype "passive"))
      (node (ref "CC14") (pin "1") (pinfunction "1_1") (pintype "passive"))
      (node (ref "NT_CSHORT") (pin "1") (pinfunction "1_1") (pintype "passive"))
      (node (ref "RC14") (pin "2") (pinfunction "2_2") (pintype "passive"))
    )
    (net (code "26") (name "/C15") (class "Default")
      (node (ref "CC14") (pin "2") (pinfunction "2_2") (pintype "passive"))
      (node (ref "CC15") (pin "2") (pinfunction "2_2") (pintype "passive"))
      (node (ref "DS_1") (pin "1") (pinfunction "K_1") (pintype "passive"))
      (node (ref "NT_C14") (pin "1") (pinfunction "1_1") (pintype "passive"))
      (node (ref "QBD_1B") (pin "2") (pinfunction "D_2") (pintype "passive"))
      (node (ref "QBD_2B") (pin "2") (pinfunction "D_2") (pintype "passive"))
      (node (ref "QBD_3B") (pin "2") (pinfunction "D_2") (pintype "passive"))
      (node (ref "QBD_4B") (pin "2") (pinfunction "D_2") (pintype "passive"))
      (node (ref "QBD_5B") (pin "2") (pinfunction "D_2") (pintype "passive"))
      (node (ref "QSHUNT") (pin "3") (pinfunction "D_3") (pintype "passive"))
    )
    (net (code "27") (name "/CAN_RX") (class "Default")
      (node (ref "U100") (pin "45") (pinfunction "PB8_45") (pintype "bidirectional"))
    )
    (net (code "28") (name "/CAN_TX") (class "Default")
      (node (ref "U100") (pin "46") (pinfunction "PB9_46") (pintype "bidirectional"))
    )
    (net (code "29") (name "/CC1") (class "Default")
      (node (ref "J100") (pin "A5") (pinfunction "CC1_A5") (pintype "passive"))
      (node (ref "J101") (pin "A5") (pinfunction "CC1_A5") (pintype "passive"))
      (node (ref "R108") (pin "2") (pinfunction "2_2") (pintype "passive"))
    )
    (net (code "30") (name "/CC2") (class "Default")
      (node (ref "J100") (pin "B5") (pinfunction "CC2_B5") (pintype "passive"))
      (node (ref "J101") (pin "B5") (pinfunction "CC2_B5") (pintype "passive"))
      (node (ref "R109") (pin "2") (pinfunction "2_2") (pintype "passive"))
    )
    (net (code "31") (name "/CELL1") (class "Default")
      (node (ref "J1") (pin "2") (pinfunction "1_2") (pintype "passive"))
      (node (ref "J1") (pin "4") (pinfunction "4_4") (pintype "passive"))
      (node (ref "NT_C1") (pin "1") (pinfunction "1_1") (pintype "passive"))
    )
    (net (code "32") (name "/CELL2") (class "Default")
      (node (ref "J1") (pin "3") (pinfunction "3_3") (pintype "passive"))
      (node (ref "J2") (pin "1") (pinfunction "1_1") (pintype "passive"))
      (node (ref "NT_C2") (pin "2") (pinfunction "2_2") (pintype "passive"))
    )
    (net (code "33") (name "/CELL3") (class "Default")
      (node (ref "J2") (pin "2") (pinfunction "1_2") (pintype "passive"))
      (node (ref "J2") (pin "4") (pinfunction "4_4") (pintype "passive"))
      (node (ref "NT_C3") (pin "1") (pinfunction "1_1") (pintype "passive"))
    )
    (net (code "34") (name "/CELL4") (class "Default")
      (node (ref "J2") (pin "3") (pinfunction "3_3") (pintype "passive"))
      (node (ref "J3") (pin "1") (pinfunction "1_1") (pintype "passive"))
      (node (ref "NT_C4") (pin "2") (pinfunction "2_2") (pintype "passive"))
    )
    (net (code "35") (name "/CELL5") (class "Default")
      (node (ref "J3") (pin "2") (pinfunction "1_2") (pintype "passive"))
      (node (ref "J3") (pin "4") (pinfunction "4_4") (pintype "passive"))
      (node (ref "NT_C5") (pin "1") (pinfunction "1_1") (pintype "passive"))
    )
    (net (code "36") (name "/CELL6") (class "Default")
      (node (ref "J3") (pin "3") (pinfunction "3_3") (pintype "passive"))
      (node (ref "J4") (pin "1") (pinfunction "1_1") (pintype "passive"))
      (node (ref "NT_C6") (pin "2") (pinfunction "2_2") (pintype "passive"))
    )
    (net (code "37") (name "/CELL7") (class "Default")
      (node (ref "J4") (pin "2") (pinfunction "1_2") (pintype "passive"))
      (node (ref "J4") (pin "4") (pinfunction "4_4") (pintype "passive"))
      (node (ref "NT_C7") (pin "1") (pinfunction "1_1") (pintype "passive"))
    )
    (net (code "38") (name "/CELL8") (class "Default")
      (node (ref "J4") (pin "3") (pinfunction "3_3") (pintype "passive"))
      (node (ref "J5") (pin "1") (pinfunction "1_1") (pintype "passive"))
      (node (ref "NT_C8") (pin "2") (pinfunction "2_2") (pintype "passive"))
    )
    (net (code "39") (name "/CELL9") (class "Default")
      (node (ref "J5") (pin "2") (pinfunction "1_2") (pintype "passive"))
      (node (ref "J5") (pin "4") (pinfunction "4_4") (pintype "passive"))
      (node (ref "NT_C9") (pin "1") (pinfunction "1_1") (pintype "passive"))
    )
    (net (code "40") (name "/CELL10") (class "Default")
      (node (ref "J5") (pin "3") (pinfunction "3_3") (pintype "passive"))
      (node (ref "J6") (pin "1") (pinfunction "1_1") (pintype "passive"))
      (node (ref "NT_C10") (pin "2") (pinfunction "2_2") (pintype "passive"))
    )
    (net (code "41") (name "/CELL11") (class "Default")
      (node (ref "J6") (pin "2") (pinfunction "1_2") (pintype "passive"))
      (node (ref "J6") (pin "4") (pinfunction "4_4") (pintype "passive"))
      (node (ref "NT_C11") (pin "1") (pinfunction "1_1") (pintype "passive"))
    )
    (net (code "42") (name "/CELL12") (class "Default")
      (node (ref "J6") (pin "3") (pinfunction "3_3") (pintype "passive"))
      (node (ref "J7") (pin "1") (pinfunction "1_1") (pintype "passive"))
      (node (ref "NT_C12") (pin "2") (pinfunction "2_2") (pintype "passive"))
    )
    (net (code "43") (name "/CELL13") (class "Default")
      (node (ref "J7") (pin "2") (pinfunction "1_2") (pintype "passive"))
      (node (ref "J7") (pin "4") (pinfunction "4_4") (pintype "passive"))
      (node (ref "NT_C13") (pin "1") (pinfunction "1_1") (pintype "passive"))
    )
    (net (code "44") (name "/CELL14") (class "Default")
      (node (ref "J7") (pin "3") (pinfunction "3_3") (pintype "passive"))
      (node (ref "NT_C14") (pin "2") (pinfunction "2_2") (pintype "passive"))
    )
    (net (code "45") (name "/CHIP_SELECT") (class "Default")
      (node (ref "U100") (pin "4") (pinfunction "PC15-OSC32_OUT_4") (pintype "bidirectional"))
    )
    (net (code "46") (name "/COS") (class "Default")
      (node (ref "U100") (pin "16") (pinfunction "PA6_16") (pintype "bidirectional"))
    )
    (net (code "47") (name "/DATA_BUS_A0") (class "Default")
      (node (ref "D_ADR_0") (pin "1") (pinfunction "K_1") (pintype "passive"))
      (node (ref "U100") (pin "40") (pinfunction "PB4_40") (pintype "bidirectional"))
      (node (ref "U2") (pin "10") (pinfunction "S0_10") (pintype "passive"))
    )
    (net (code "48") (name "/DATA_BUS_A1") (class "Default")
      (node (ref "D_ADR_1") (pin "1") (pinfunction "K_1") (pintype "passive"))
      (node (ref "U100") (pin "41") (pinfunction "PB5_41") (pintype "bidirectional"))
      (node (ref "U2") (pin "11") (pinfunction "S1_11") (pintype "passive"))
    )
    (net (code "49") (name "/DATA_BUS_A2") (class "Default")
      (node (ref "D_ADR_2") (pin "1") (pinfunction "K_1") (pintype "passive"))
      (node (ref "U100") (pin "39") (pinfunction "PB3_39") (pintype "bidirectional"))
      (node (ref "U2") (pin "14") (pinfunction "S2_14") (pintype "passive"))
    )
    (net (code "50") (name "/DATA_BUS_A3") (class "Default")
      (node (ref "D_ADR_3") (pin "1") (pinfunction "K_1") (pintype "passive"))
      (node (ref "U100") (pin "31") (pinfunction "PA10_31") (pintype "bidirectional"))
      (node (ref "U2") (pin "13") (pinfunction "S3_13") (pintype "passive"))
    )
    (net (code "51") (name "/DATA_BUS_A4") (class "Default")
      (node (ref "D_ADR_4") (pin "1") (pinfunction "K_1") (pintype "passive"))
      (node (ref "U100") (pin "30") (pinfunction "PA9_30") (pintype "bidirectional"))
    )
    (net (code "52") (name "/DATA_BUS_A5") (class "Default")
      (node (ref "D_ADR_5") (pin "1") (pinfunction "K_1") (pintype "passive"))
      (node (ref "U100") (pin "29") (pinfunction "PA8_29") (pintype "bidirectional"))
    )
    (net (code "53") (name "/DATA_BUS_A6") (class "Default")
      (node (ref "D_ADR_6") (pin "1") (pinfunction "K_1") (pintype "passive"))
      (node (ref "U100") (pin "25") (pinfunction "PB12_25") (pintype "bidirectional"))
    )
    (net (code "54") (name "/GND") (class "Default")
      (node (ref "C100") (pin "1") (pinfunction "1_1") (pintype "passive"))
      (node (ref "C101") (pin "1") (pinfunction "1_1") (pintype "passive"))
      (node (ref "C102") (pin "1") (pinfunction "1_1") (pintype "passive"))
      (node (ref "C103") (pin "1") (pinfunction "1_1") (pintype "passive"))
      (node (ref "C104") (pin "1") (pinfunction "1_1") (pintype "passive"))
      (node (ref "C106") (pin "1") (pinfunction "1_1") (pintype "passive"))
      (node (ref "C107") (pin "1") (pinfunction "1_1") (pintype "passive"))
      (node (ref "C2") (pin "1") (pinfunction "1_1") (pintype "passive"))
      (node (ref "CAP1") (pin "2") (pinfunction "2_2") (pintype "passive"))
      (node (ref "CAPSRC") (pin "2") (pinfunction "2_2") (pintype "passive"))
      (node (ref "CC0A") (pin "2") (pinfunction "2_2") (pintype "passive"))
      (node (ref "CC0B") (pin "1") (pinfunction "1_1") (pintype "passive"))
      (node (ref "CR1") (pin "2") (pinfunction "2_2") (pintype "passive"))
      (node (ref "CR2") (pin "2") (pinfunction "2_2") (pintype "passive"))
      (node (ref "CR3") (pin "2") (pinfunction "2_2") (pintype "passive"))
      (node (ref "CSNS0") (pin "1") (pinfunction "1_1") (pintype "passive"))
      (node (ref "CSNS2") (pin "2") (pinfunction "2_2") (pintype "passive"))
      (node (ref "DS_VCC") (pin "2") (pinfunction "A_2") (pintype "passive"))
      (node (ref "J1") (pin "1") (pinfunction "1_1") (pintype "passive"))
      (node (ref "J100") (pin "0") (pinfunction "SHLD_0") (pintype "passive"))
      (node (ref "J100") (pin "A12_B1") (pinfunction "GND_A12_B1") (pintype "passive"))
      (node (ref "J100") (pin "A1_B12") (pinfunction "GND_A1_B12") (pintype "passive"))
      (node (ref "J101") (pin "0") (pinfunction "SHLD_0") (pintype "passive"))
      (node (ref "J101") (pin "A12_B1") (pinfunction "GND_A12_B1") (pintype "passive"))
      (node (ref "J101") (pin "A1_B12") (pinfunction "GND_A1_B12") (pintype "passive"))
      (node (ref "LED_1") (pin "1") (pinfunction "K_1") (pintype "passive"))
      (node (ref "LED_1A") (pin "1") (pinfunction "K_1") (pintype "passive"))
      (node (ref "LED_2") (pin "1") (pinfunction "K_1") (pintype "passive"))
      (node (ref "LED_2A") (pin "1") (pinfunction "K_1") (pintype "passive"))
      (node (ref "LED_3") (pin "1") (pinfunction "K_1") (pintype "passive"))
      (node (ref "LED_3A") (pin "1") (pinfunction "K_1") (pintype "passive"))
      (node (ref "NT_1") (pin "2") (pinfunction "2_2") (pintype "passive"))
      (node (ref "NT_C0") (pin "2") (pinfunction "2_2") (pintype "passive"))
      (node (ref "Q18") (pin "2") (pinfunction "S_2") (pintype "passive"))
      (node (ref "QBEN") (pin "2") (pinfunction "S_2") (pintype "passive"))
      (node (ref "QBENR") (pin "2") (pinfunction "2_2") (pintype "passive"))
      (node (ref "R102") (pin "1") (pinfunction "1_1") (pintype "passive"))
      (node (ref "R108") (pin "1") (pinfunction "1_1") (pintype "passive"))
      (node (ref "R109") (pin "1") (pinfunction "1_1") (pintype "passive"))
      (node (ref "R110") (pin "2") (pinfunction "2_2") (pintype "passive"))
      (node (ref "RSNS") (pin "1") (pinfunction "1_1") (pintype "passive"))
      (node (ref "RSNSP") (pin "1") (pinfunction "1_1") (pintype "passive"))
      (node (ref "R_Q18G") (pin "2") (pinfunction "2_2") (pintype "passive"))
      (node (ref "R_STBY2") (pin "1") (pinfunction "1_1") (pintype "passive"))
      (node (ref "R_VBUS3") (pin "1") (pinfunction "1_1") (pintype "passive"))
      (node (ref "SW_WAKE") (pin "2") (pinfunction "2_2") (pintype "passive"))
      (node (ref "U1") (pin "3") (pinfunction "VSS_3") (pintype "passive"))
      (node (ref "U100") (pin "23") (pinfunction "VSS_1_23") (pintype "power_in"))
      (node (ref "U100") (pin "35") (pinfunction "VSS_2_35") (pintype "power_in"))
      (node (ref "U100") (pin "44") (pinfunction "BOOT0_44") (pintype "input"))
      (node (ref "U100") (pin "47") (pinfunction "VSS_3_47") (pintype "power_in"))
      (node (ref "U101") (pin "1") (pinfunction "VSS_1") (pintype "power_in"))
      (node (ref "U2") (pin "12") (pinfunction "VSS_12") (pintype "power_in"))
    )
    (net (code "55") (name "/GQBD") (class "Default")
      (node (ref "DBD_2") (pin "2") (pinfunction "A_2") (pintype "passive"))
      (node (ref "GQBDR") (pin "2") (pinfunction "2_2") (pintype "passive"))
      (node (ref "QBD_1A") (pin "1") (pinfunction "G_1") (pintype "passive"))
      (node (ref "QBD_1B") (pin "1") (pinfunction "G_1") (pintype "passive"))
      (node (ref "QBD_2A") (pin "1") (pinfunction "G_1") (pintype "passive"))
      (node (ref "QBD_2B") (pin "1") (pinfunction "G_1") (pintype "passive"))
      (node (ref "QBD_3A") (pin "1") (pinfunction "G_1") (pintype "passive"))
      (node (ref "QBD_3B") (pin "1") (pinfunction "G_1") (pintype "passive"))
      (node (ref "QBD_4A") (pin "1") (pinfunction "G_1") (pintype "passive"))
      (node (ref "QBD_4B") (pin "1") (pinfunction "G_1") (pintype "passive"))
      (node (ref "QBD_5A") (pin "1") (pinfunction "G_1") (pintype "passive"))
      (node (ref "QBD_5B") (pin "1") (pinfunction "G_1") (pintype "passive"))
      (node (ref "RBEN") (pin "2") (pinfunction "2_2") (pintype "passive"))
    )
    (net (code "56") (name "/GQS") (class "Default")
      (node (ref "DBD_1") (pin "1") (pinfunction "K_1") (pintype "passive"))
      (node (ref "GQBDR") (pin "1") (pinfunction "1_1") (pintype "passive"))
      (node (ref "QBD_1A") (pin "3") (pinfunction "S_3") (pintype "passive"))
      (node (ref "QBD_1B") (pin "3") (pinfunction "S_3") (pintype "passive"))
      (node (ref "QBD_2A") (pin "3") (pinfunction "S_3") (pintype "passive"))
      (node (ref "QBD_2B") (pin "3") (pinfunction "S_3") (pintype "passive"))
      (node (ref "QBD_3A") (pin "3") (pinfunction "S_3") (pintype "passive"))
      (node (ref "QBD_3B") (pin "3") (pinfunction "S_3") (pintype "passive"))
      (node (ref "QBD_4A") (pin "3") (pinfunction "S_3") (pintype "passive"))
      (node (ref "QBD_4B") (pin "3") (pinfunction "S_3") (pintype "passive"))
      (node (ref "QBD_5A") (pin "3") (pinfunction "S_3") (pintype "passive"))
      (node (ref "QBD_5B") (pin "3") (pinfunction "S_3") (pintype "passive"))
    )
    (net (code "57") (name "/HOTPLUG_OUT") (class "Default")
      (node (ref "D_3V3_O") (pin "1") (pinfunction "K_1") (pintype "passive"))
    )
    (net (code "58") (name "/I2C_A0") (class "Default")
      (node (ref "D_ADR_0") (pin "2") (pinfunction "A_2") (pintype "passive"))
    )
    (net (code "59") (name "/I2C_A1") (class "Default")
      (node (ref "D_ADR_1") (pin "2") (pinfunction "A_2") (pintype "passive"))
    )
    (net (code "60") (name "/I2C_A2") (class "Default")
      (node (ref "D_ADR_2") (pin "2") (pinfunction "A_2") (pintype "passive"))
    )
    (net (code "61") (name "/I2C_A3") (class "Default")
      (node (ref "D_ADR_3") (pin "2") (pinfunction "A_2") (pintype "passive"))
    )
    (net (code "62") (name "/I2C_A4") (class "Default")
      (node (ref "D_ADR_4") (pin "2") (pinfunction "A_2") (pintype "passive"))
    )
    (net (code "63") (name "/I2C_A5") (class "Default")
      (node (ref "D_ADR_5") (pin "2") (pinfunction "A_2") (pintype "passive"))
    )
    (net (code "64") (name "/I2C_A6") (class "Default")
      (node (ref "D_ADR_6") (pin "2") (pinfunction "A_2") (pintype "passive"))
    )
    (net (code "65") (name "/I2C_ASNS") (class "Default")
      (node (ref "D_ADR_VCC") (pin "1") (pinfunction "K_1") (pintype "passive"))
    )
    (net (code "66") (name "/LED_1") (class "Default")
      (node (ref "RLED_1") (pin "2") (pinfunction "2_2") (pintype "passive"))
      (node (ref "U100") (pin "13") (pinfunction "PA3_13") (pintype "bidirectional"))
    )
    (net (code "67") (name "/LED_2") (class "Default")
      (node (ref "RLED_2") (pin "2") (pinfunction "2_2") (pintype "passive"))
      (node (ref "U100") (pin "12") (pinfunction "PA2_12") (pintype "bidirectional"))
    )
    (net (code "68") (name "/LED_3") (class "Default")
      (node (ref "RLED_3") (pin "2") (pinfunction "2_2") (pintype "passive"))
      (node (ref "U100") (pin "11") (pinfunction "PA1_11") (pintype "bidirectional"))
    )
    (net (code "69") (name "/NRST") (class "Default")
      (node (ref "C106") (pin "2") (pinfunction "2_2") (pintype "passive"))
      (node (ref "U100") (pin "7") (pinfunction "NRST_7") (pintype "bidirectional"))
    )
    (net (code "70") (name "/PACK+") (class "Default")
      (node (ref "QBD_1A") (pin "2") (pinfunction "D_2") (pintype "passive"))
      (node (ref "QBD_2A") (pin "2") (pinfunction "D_2") (pintype "passive"))
      (node (ref "QBD_3A") (pin "2") (pinfunction "D_2") (pintype "passive"))
      (node (ref "QBD_4A") (pin "2") (pinfunction "D_2") (pintype "passive"))
      (node (ref "QBD_5A") (pin "2") (pinfunction "D_2") (pintype "passive"))
      (node (ref "R_VBUS1") (pin "2") (pinfunction "2_2") (pintype "passive"))
    )
    (net (code "71") (name "/PACK-") (class "Default")
      (node (ref "RSNS") (pin "2") (pinfunction "2_2") (pintype "passive"))
      (node (ref "RSNSN") (pin "1") (pinfunction "1_1") (pintype "passive"))
    )
    (net (code "72") (name "/REGSRC") (class "Default")
      (node (ref "CAPSRC") (pin "1") (pinfunction "1_1") (pintype "passive"))
      (node (ref "RSHUNT3") (pin "1") (pinfunction "1_1") (pintype "passive"))
      (node (ref "U1") (pin "9") (pinfunction "REGSRC_9") (pintype "passive"))
    )
    (net (code "73") (name "/SIN") (class "Default")
      (node (ref "U100") (pin "17") (pinfunction "PA7_17") (pintype "bidirectional"))
    )
    (net (code "74") (name "/SRN") (class "Default")
      (node (ref "CSNS0") (pin "2") (pinfunction "2_2") (pintype "passive"))
      (node (ref "CSNS1") (pin "1") (pinfunction "1_1") (pintype "passive"))
      (node (ref "RSNSN") (pin "2") (pinfunction "2_2") (pintype "passive"))
      (node (ref "U1") (pin "43") (pinfunction "SRN_43") (pintype "passive"))
    )
    (net (code "75") (name "/SRP") (class "Default")
      (node (ref "CSNS1") (pin "2") (pinfunction "2_2") (pintype "passive"))
      (node (ref "CSNS2") (pin "1") (pinfunction "1_1") (pintype "passive"))
      (node (ref "RSNSP") (pin "2") (pinfunction "2_2") (pintype "passive"))
      (node (ref "U1") (pin "42") (pinfunction "SRP_42") (pintype "passive"))
    )
    (net (code "76") (name "/SWCLK") (class "Default")
      (node (ref "U100") (pin "37") (pinfunction "PA14_37") (pintype "bidirectional"))
    )
    (net (code "77") (name "/SWDIO") (class "Default")
      (node (ref "U100") (pin "34") (pinfunction "PA13_34") (pintype "bidirectional"))
    )
    (net (code "78") (name "/TS2") (class "Default")
      (node (ref "U1") (pin "13") (pinfunction "TS2_13") (pintype "passive"))
    )
    (net (code "79") (name "/TS3") (class "Default")
      (node (ref "U1") (pin "18") (pinfunction "TS3_18") (pintype "passive"))
    )
    (net (code "80") (name "/TS_0") (class "Default")
      (node (ref "RT_0B") (pin "1") (pinfunction "1_1") (pintype "passive"))
      (node (ref "TS_C1_A") (pin "2") (pinfunction "2_2") (pintype "passive"))
      (node (ref "TS_C1_B") (pin "2") (pinfunction "2_2") (pintype "passive"))
      (node (ref "U2") (pin "9") (pinfunction "Y0_9") (pintype "passive"))
    )
    (net (code "81") (name "/TS_1") (class "Default")
      (node (ref "RT_1B") (pin "1") (pinfunction "1_1") (pintype "passive"))
      (node (ref "TS_C2_A") (pin "2") (pinfunction "2_2") (pintype "passive"))
      (node (ref "TS_C2_B") (pin "2") (pinfunction "2_2") (pintype "passive"))
      (node (ref "U2") (pin "8") (pinfunction "Y1_8") (pintype "passive"))
    )
    (net (code "82") (name "/TS_2") (class "Default")
      (node (ref "RT_2B") (pin "1") (pinfunction "1_1") (pintype "passive"))
      (node (ref "TS_C3_A") (pin "2") (pinfunction "2_2") (pintype "passive"))
      (node (ref "TS_C3_B") (pin "2") (pinfunction "2_2") (pintype "passive"))
      (node (ref "U2") (pin "7") (pinfunction "Y2_7") (pintype "passive"))
    )
    (net (code "83") (name "/TS_3") (class "Default")
      (node (ref "RT_3B") (pin "1") (pinfunction "1_1") (pintype "passive"))
      (node (ref "TS_C4_A") (pin "2") (pinfunction "2_2") (pintype "passive"))
      (node (ref "TS_C4_B") (pin "2") (pinfunction "2_2") (pintype "passive"))
      (node (ref "U2") (pin "6") (pinfunction "Y3_6") (pintype "passive"))
    )
    (net (code "84") (name "/TS_4") (class "Default")
      (node (ref "RT_4B") (pin "1") (pinfunction "1_1") (pintype "passive"))
      (node (ref "TS_C5_A") (pin "2") (pinfunction "2_2") (pintype "passive"))
      (node (ref "TS_C5_B") (pin "2") (pinfunction "2_2") (pintype "passive"))
      (node (ref "U2") (pin "5") (pinfunction "Y4_5") (pintype "passive"))
    )
    (net (code "85") (name "/TS_5") (class "Default")
      (node (ref "RT_5B") (pin "1") (pinfunction "1_1") (pintype "passive"))
      (node (ref "TS_C6_A") (pin "2") (pinfunction "2_2") (pintype "passive"))
      (node (ref "TS_C6_B") (pin "2") (pinfunction "2_2") (pintype "passive"))
      (node (ref "U2") (pin "4") (pinfunction "Y5_4") (pintype "passive"))
    )
    (net (code "86") (name "/TS_6") (class "Default")
      (node (ref "RT_6B") (pin "1") (pinfunction "1_1") (pintype "passive"))
      (node (ref "TS_C7_A") (pin "2") (pinfunction "2_2") (pintype "passive"))
      (node (ref "TS_C7_B") (pin "2") (pinfunction "2_2") (pintype "passive"))
      (node (ref "U2") (pin "3") (pinfunction "Y6_3") (pintype "passive"))
    )
    (net (code "87") (name "/TS_7") (class "Default")
      (node (ref "RT_7B") (pin "1") (pinfunction "1_1") (pintype "passive"))
      (node (ref "TS_C8_A") (pin "2") (pinfunction "2_2") (pintype "passive"))
      (node (ref "TS_C8_B") (pin "2") (pinfunction "2_2") (pintype "passive"))
      (node (ref "U2") (pin "2") (pinfunction "Y7_2") (pintype "passive"))
    )
    (net (code "88") (name "/TS_8") (class "Default")
      (node (ref "RT_8B") (pin "1") (pinfunction "1_1") (pintype "passive"))
      (node (ref "U2") (pin "23") (pinfunction "Y8_23") (pintype "passive"))
    )
    (net (code "89") (name "/TS_9") (class "Default")
      (node (ref "RT_9B") (pin "1") (pinfunction "1_1") (pintype "passive"))
      (node (ref "TS_C9_A") (pin "2") (pinfunction "2_2") (pintype "passive"))
      (node (ref "TS_C9_B") (pin "2") (pinfunction "2_2") (pintype "passive"))
      (node (ref "U2") (pin "22") (pinfunction "Y9_22") (pintype "passive"))
    )
    (net (code "90") (name "/TS_10") (class "Default")
      (node (ref "RT_10B") (pin "1") (pinfunction "1_1") (pintype "passive"))
      (node (ref "TS_C10_A") (pin "2") (pinfunction "2_2") (pintype "passive"))
      (node (ref "TS_C10_B") (pin "2") (pinfunction "2_2") (pintype "passive"))
      (node (ref "U2") (pin "21") (pinfunction "Y10_21") (pintype "passive"))
    )
    (net (code "91") (name "/TS_11") (class "Default")
      (node (ref "RT_11B") (pin "1") (pinfunction "1_1") (pintype "passive"))
      (node (ref "TS_C11_A") (pin "2") (pinfunction "2_2") (pintype "passive"))
      (node (ref "TS_C11_B") (pin "2") (pinfunction "2_2") (pintype "passive"))
      (node (ref "U2") (pin "20") (pinfunction "Y11_20") (pintype "passive"))
    )
    (net (code "92") (name "/TS_12") (class "Default")
      (node (ref "RT_12B") (pin "1") (pinfunction "1_1") (pintype "passive"))
      (node (ref "TS_C12_A") (pin "2") (pinfunction "2_2") (pintype "passive"))
      (node (ref "TS_C12_B") (pin "2") (pinfunction "2_2") (pintype "passive"))
      (node (ref "U2") (pin "19") (pinfunction "Y12_19") (pintype "passive"))
    )
    (net (code "93") (name "/TS_13") (class "Default")
      (node (ref "RT_13B") (pin "1") (pinfunction "1_1") (pintype "passive"))
      (node (ref "TS_C13A") (pin "2") (pinfunction "2_2") (pintype "passive"))
      (node (ref "TS_C13_B") (pin "2") (pinfunction "2_2") (pintype "passive"))
      (node (ref "U2") (pin "18") (pinfunction "Y13_18") (pintype "passive"))
    )
    (net (code "94") (name "/TS_14") (class "Default")
      (node (ref "RT_14B") (pin "1") (pinfunction "1_1") (pintype "passive"))
      (node (ref "TS_C14_A") (pin "2") (pinfunction "2_2") (pintype "passive"))
      (node (ref "TS_C14_B") (pin "2") (pinfunction "2_2") (pintype "passive"))
      (node (ref "U2") (pin "17") (pinfunction "Y14_17") (pintype "passive"))
    )
    (net (code "95") (name "/TS_15") (class "Default")
      (node (ref "CTS_15") (pin "2") (pinfunction "2_2") (pintype "passive"))
      (node (ref "RTS2") (pin "2") (pinfunction "2_2") (pintype "passive"))
      (node (ref "RT_15B") (pin "1") (pinfunction "1_1") (pintype "passive"))
      (node (ref "U2") (pin "16") (pinfunction "Y15_16") (pintype "passive"))
    )
    (net (code "96") (name "/TS_A_GND") (class "Default")
      (node (ref "TSQ1a") (pin "3") (pinfunction "D_3") (pintype "passive"))
      (node (ref "TS_C10_A") (pin "1") (pinfunction "1_1") (pintype "passive"))
      (node (ref "TS_C11_A") (pin "1") (pinfunction "1_1") (pintype "passive"))
      (node (ref "TS_C12_A") (pin "1") (pinfunction "1_1") (pintype "passive"))
      (node (ref "TS_C13A") (pin "1") (pinfunction "1_1") (pintype "passive"))
      (node (ref "TS_C14_A") (pin "1") (pinfunction "1_1") (pintype "passive"))
      (node (ref "TS_C1_A") (pin "1") (pinfunction "1_1") (pintype "passive"))
      (node (ref "TS_C2_A") (pin "1") (pinfunction "1_1") (pintype "passive"))
      (node (ref "TS_C3_A") (pin "1") (pinfunction "1_1") (pintype "passive"))
      (node (ref "TS_C4_A") (pin "1") (pinfunction "1_1") (pintype "passive"))
      (node (ref "TS_C5_A") (pin "1") (pinfunction "1_1") (pintype "passive"))
      (node (ref "TS_C6_A") (pin "1") (pinfunction "1_1") (pintype "passive"))
      (node (ref "TS_C7_A") (pin "1") (pinfunction "1_1") (pintype "passive"))
      (node (ref "TS_C8_A") (pin "1") (pinfunction "1_1") (pintype "passive"))
      (node (ref "TS_C9_A") (pin "1") (pinfunction "1_1") (pintype "passive"))
    )
    (net (code "97") (name "/TS_B_GND") (class "Default")
      (node (ref "TSQ1b") (pin "3") (pinfunction "D_3") (pintype "passive"))
      (node (ref "TS_C10_B") (pin "1") (pinfunction "1_1") (pintype "passive"))
      (node (ref "TS_C11_B") (pin "1") (pinfunction "1_1") (pintype "passive"))
      (node (ref "TS_C12_B") (pin "1") (pinfunction "1_1") (pintype "passive"))
      (node (ref "TS_C13_B") (pin "1") (pinfunction "1_1") (pintype "passive"))
      (node (ref "TS_C14_B") (pin "1") (pinfunction "1_1") (pintype "passive"))
      (node (ref "TS_C1_B") (pin "1") (pinfunction "1_1") (pintype "passive"))
      (node (ref "TS_C2_B") (pin "1") (pinfunction "1_1") (pintype "passive"))
      (node (ref "TS_C3_B") (pin "1") (pinfunction "1_1") (pintype "passive"))
      (node (ref "TS_C4_B") (pin "1") (pinfunction "1_1") (pintype "passive"))
      (node (ref "TS_C5_B") (pin "1") (pinfunction "1_1") (pintype "passive"))
      (node (ref "TS_C6_B") (pin "1") (pinfunction "1_1") (pintype "passive"))
      (node (ref "TS_C7_B") (pin "1") (pinfunction "1_1") (pintype "passive"))
      (node (ref "TS_C8_B") (pin "1") (pinfunction "1_1") (pintype "passive"))
      (node (ref "TS_C9_B") (pin "1") (pinfunction "1_1") (pintype "passive"))
    )
    (net (code "98") (name "/TS_EN_A") (class "Default")
      (node (ref "D1") (pin "2") (pinfunction "A_2") (pintype "passive"))
      (node (ref "TSQ1a") (pin "1") (pinfunction "G_1") (pintype "passive"))
      (node (ref "U100") (pin "27") (pinfunction "PB14_27") (pintype "bidirectional"))
    )
    (net (code "99") (name "/TS_EN_B") (class "Default")
      (node (ref "D2") (pin "2") (pinfunction "A_2") (pintype "passive"))
      (node (ref "TSQ1b") (pin "1") (pinfunction "G_1") (pintype "passive"))
      (node (ref "U100") (pin "28") (pinfunction "PB15_28") (pintype "bidirectional"))
    )
    (net (code "100") (name "/TS_EN_MUX") (class "Default")
      (node (ref "D1") (pin "1") (pinfunction "K_1") (pintype "passive"))
      (node (ref "D2") (pin "1") (pinfunction "K_1") (pintype "passive"))
      (node (ref "U2") (pin "15") (pinfunction "E_15") (pintype "passive"))
    )
    (net (code "101") (name "/TS_MULTIPLEXED") (class "Default")
      (node (ref "R2") (pin "2") (pinfunction "2_2") (pintype "passive"))
      (node (ref "U2") (pin "1") (pinfunction "Z_1") (pintype "passive"))
    )
    (net (code "102") (name "/TS_MUX_FILTERED") (class "Default")
      (node (ref "C2") (pin "2") (pinfunction "2_2") (pintype "passive"))
      (node (ref "R2") (pin "1") (pinfunction "1_1") (pintype "passive"))
      (node (ref "U100") (pin "15") (pinfunction "PA5_15") (pintype "bidirectional"))
    )
    (net (code "103") (name "/USB_DM") (class "Default")
      (node (ref "R100") (pin "1") (pinfunction "1_1") (pintype "passive"))
      (node (ref "R103") (pin "1") (pinfunction "1_1") (pintype "passive"))
    )
    (net (code "104") (name "/USB_DM_P") (class "Default")
      (node (ref "J100") (pin "A7") (pinfunction "D1_N_A7") (pintype "passive"))
      (node (ref "J100") (pin "B7") (pinfunction "D2_N_B7") (pintype "passive"))
      (node (ref "J101") (pin "A7") (pinfunction "D1_N_A7") (pintype "passive"))
      (node (ref "J101") (pin "B7") (pinfunction "D2_N_B7") (pintype "passive"))
      (node (ref "R103") (pin "2") (pinfunction "2_2") (pintype "passive"))
    )
    (net (code "105") (name "/USB_DM_R") (class "Default")
      (node (ref "R100") (pin "2") (pinfunction "2_2") (pintype "passive"))
      (node (ref "U100") (pin "32") (pinfunction "PA11_32") (pintype "bidirectional"))
    )
    (net (code "106") (name "/USB_DP") (class "Default")
      (node (ref "R101") (pin "1") (pinfunction "1_1") (pintype "passive"))
      (node (ref "R104") (pin "1") (pinfunction "1_1") (pintype "passive"))
    )
    (net (code "107") (name "/USB_DP_P") (class "Default")
      (node (ref "J100") (pin "A6") (pinfunction "D1_P_A6") (pintype "passive"))
      (node (ref "J100") (pin "B6") (pinfunction "D2_P_B6") (pintype "passive"))
      (node (ref "J101") (pin "A6") (pinfunction "D1_P_A6") (pintype "passive"))
      (node (ref "J101") (pin "B6") (pinfunction "D2_P_B6") (pintype "passive"))
      (node (ref "R104") (pin "2") (pinfunction "2_2") (pintype "passive"))
    )
    (net (code "108") (name "/USB_DP_R") (class "Default")
      (node (ref "R101") (pin "2") (pinfunction "2_2") (pintype "passive"))
      (node (ref "R106") (pin "1") (pinfunction "1_1") (pintype "passive"))
      (node (ref "U100") (pin "33") (pinfunction "PA12_33") (pintype "bidirectional"))
    )
    (net (code "109") (name "/VBUS_SNS") (class "Default")
      (node (ref "R_VBUS2") (pin "1") (pinfunction "1_1") (pintype "passive"))
      (node (ref "R_VBUS3") (pin "2") (pinfunction "2_2") (pintype "passive"))
      (node (ref "U100") (pin "18") (pinfunction "PB0_18") (pintype "bidirectional"))
    )
    (net (code "110") (name "/VC5x") (class "Default")
      (node (ref "CAP2") (pin "2") (pinfunction "2_2") (pintype "passive"))
      (node (ref "CC5A") (pin "2") (pinfunction "2_2") (pintype "passive"))
      (node (ref "CC5B") (pin "1") (pinfunction "1_1") (pintype "passive"))
      (node (ref "DC5") (pin "1") (pinfunction "K_1") (pintype "passive"))
      (node (ref "RSHUNT") (pin "1") (pinfunction "1_1") (pintype "passive"))
      (node (ref "U1") (pin "10") (pinfunction "VC5x_10") (pintype "passive"))
    )
    (net (code "111") (name "/VC10x") (class "Default")
      (node (ref "CAP3") (pin "2") (pinfunction "2_2") (pintype "passive"))
      (node (ref "CC10A") (pin "2") (pinfunction "2_2") (pintype "passive"))
      (node (ref "CC10B") (pin "1") (pinfunction "1_1") (pintype "passive"))
      (node (ref "DC10") (pin "1") (pinfunction "K_1") (pintype "passive"))
      (node (ref "U1") (pin "15") (pinfunction "VC10x_15") (pintype "passive"))
    )
    (net (code "112") (name "/VCC_3V3") (class "Default")
      (node (ref "C102") (pin "2") (pinfunction "2_2") (pintype "passive"))
      (node (ref "C103") (pin "2") (pinfunction "2_2") (pintype "passive"))
      (node (ref "C104") (pin "2") (pinfunction "2_2") (pintype "passive"))
      (node (ref "D_3V3_O") (pin "2") (pinfunction "A_2") (pintype "passive"))
      (node (ref "L100") (pin "2") (pinfunction "2_2") (pintype "passive"))
      (node (ref "Q_3V3") (pin "2") (pinfunction "S_2") (pintype "passive"))
      (node (ref "R106") (pin "2") (pinfunction "2_2") (pintype "passive"))
      (node (ref "SW1") (pin "2") (pinfunction "2_2") (pintype "passive"))
      (node (ref "U100") (pin "1") (pinfunction "VBAT_1") (pintype "power_in"))
      (node (ref "U100") (pin "24") (pinfunction "VDD_1_24") (pintype "power_in"))
      (node (ref "U100") (pin "36") (pinfunction "VDD_2_36") (pintype "power_in"))
      (node (ref "U100") (pin "48") (pinfunction "VDD_3_48") (pintype "power_in"))
      (node (ref "U101") (pin "2") (pinfunction "Vout_2") (pintype "output"))
    )
    (net (code "113") (name "/VCC_3V3_2") (class "Default")
      (node (ref "CR1") (pin "1") (pinfunction "1_1") (pintype "passive"))
      (node (ref "CR2") (pin "1") (pinfunction "1_1") (pintype "passive"))
      (node (ref "CR3") (pin "1") (pinfunction "1_1") (pintype "passive"))
      (node (ref "NT_2") (pin "2") (pinfunction "2_2") (pintype "passive"))
      (node (ref "U1") (pin "8") (pinfunction "REGOUT_8") (pintype "passive"))
    )
    (net (code "114") (name "/VCC_3V3_SW") (class "Default")
      (node (ref "3V3R1") (pin "1") (pinfunction "1_1") (pintype "passive"))
      (node (ref "NT_2") (pin "1") (pinfunction "1_1") (pintype "passive"))
      (node (ref "Q_3V3") (pin "3") (pinfunction "D_3") (pintype "passive"))
      (node (ref "RSCL") (pin "1") (pinfunction "1_1") (pintype "passive"))
      (node (ref "RSDA") (pin "1") (pinfunction "1_1") (pintype "passive"))
      (node (ref "RT_0B") (pin "2") (pinfunction "2_2") (pintype "passive"))
      (node (ref "RT_10B") (pin "2") (pinfunction "2_2") (pintype "passive"))
      (node (ref "RT_11B") (pin "2") (pinfunction "2_2") (pintype "passive"))
      (node (ref "RT_12B") (pin "2") (pinfunction "2_2") (pintype "passive"))
      (node (ref "RT_13B") (pin "2") (pinfunction "2_2") (pintype "passive"))
      (node (ref "RT_14B") (pin "2") (pinfunction "2_2") (pintype "passive"))
      (node (ref "RT_15B") (pin "2") (pinfunction "2_2") (pintype "passive"))
      (node (ref "RT_1B") (pin "2") (pinfunction "2_2") (pintype "passive"))
      (node (ref "RT_2B") (pin "2") (pinfunction "2_2") (pintype "passive"))
      (node (ref "RT_3B") (pin "2") (pinfunction "2_2") (pintype "passive"))
      (node (ref "RT_4B") (pin "2") (pinfunction "2_2") (pintype "passive"))
      (node (ref "RT_5B") (pin "2") (pinfunction "2_2") (pintype "passive"))
      (node (ref "RT_6B") (pin "2") (pinfunction "2_2") (pintype "passive"))
      (node (ref "RT_7B") (pin "2") (pinfunction "2_2") (pintype "passive"))
      (node (ref "RT_8B") (pin "2") (pinfunction "2_2") (pintype "passive"))
      (node (ref "RT_9B") (pin "2") (pinfunction "2_2") (pintype "passive"))
      (node (ref "U2") (pin "24") (pinfunction "VCC_24") (pintype "power_in"))
    )
    (net (code "115") (name "/VCC_5V1") (class "Default")
      (node (ref "C107") (pin "2") (pinfunction "2_2") (pintype "passive"))
      (node (ref "D5V1_SB") (pin "1") (pinfunction "K_1") (pintype "passive"))
      (node (ref "DS_VCC") (pin "1") (pinfunction "K_1") (pintype "passive"))
      (node (ref "J100") (pin "A4_B9") (pinfunction "VBUS_A4_B9") (pintype "power_in"))
      (node (ref "J100") (pin "A9_B4") (pinfunction "VBUS_A9_B4") (pintype "power_in"))
      (node (ref "J101") (pin "A4_B9") (pinfunction "VBUS_A4_B9") (pintype "power_in"))
      (node (ref "J101") (pin "A9_B4") (pinfunction "VBUS_A9_B4") (pintype "power_in"))
      (node (ref "Q19") (pin "3") (pinfunction "D_3") (pintype "passive"))
      (node (ref "U101") (pin "3") (pinfunction "VIN_3") (pintype "input"))
    )
    (net (code "116") (name "/VCC_STBY") (class "Default")
      (node (ref "D5V1_SB") (pin "2") (pinfunction "A_2") (pintype "passive"))
      (node (ref "R_STBY1") (pin "2") (pinfunction "2_2") (pintype "passive"))
    )
    (net (code "117") (name "/VDDA") (class "Default")
      (node (ref "C105") (pin "2") (pinfunction "2_2") (pintype "passive"))
      (node (ref "L100") (pin "1") (pinfunction "1_1") (pintype "passive"))
      (node (ref "U100") (pin "9") (pinfunction "VDDA_9") (pintype "power_in"))
    )
    (net (code "118") (name "/VSTBY_SNS") (class "Default")
      (node (ref "R_STBY1") (pin "1") (pinfunction "1_1") (pintype "passive"))
      (node (ref "R_STBY2") (pin "2") (pinfunction "2_2") (pintype "passive"))
      (node (ref "U100") (pin "19") (pinfunction "PB1_19") (pintype "bidirectional"))
    )
    (net (code "119") (name "/WAKEUP") (class "Default")
      (node (ref "D10") (pin "2") (pinfunction "A_2") (pintype "passive"))
    )
    (net (code "120") (name "/WAKEUP_D") (class "Default")
      (node (ref "D10") (pin "1") (pinfunction "K_1") (pintype "passive"))
      (node (ref "R_WK") (pin "2") (pinfunction "2_2") (pintype "passive"))
    )
    (net (code "121") (name "/WAKEUP_D_R") (class "Default")
      (node (ref "Q18") (pin "1") (pinfunction "G_1") (pintype "passive"))
      (node (ref "R_Q18G") (pin "1") (pinfunction "1_1") (pintype "passive"))
      (node (ref "R_WK") (pin "1") (pinfunction "1_1") (pintype "passive"))
      (node (ref "U100") (pin "10") (pinfunction "PA0-WKUP_10") (pintype "bidirectional"))
    )
    (net (code "122") (name "/^PB2_BOOT1") (class "Default")
      (node (ref "R110") (pin "1") (pinfunction "1_1") (pintype "passive"))
      (node (ref "SW1") (pin "1") (pinfunction "1_1") (pintype "passive"))
      (node (ref "U100") (pin "20") (pinfunction "PB2_20") (pintype "bidirectional"))
    )
    (net (code "123") (name "Net-(DBD_1-A)") (class "Default")
      (node (ref "DBD_1") (pin "2") (pinfunction "A_2") (pintype "passive"))
      (node (ref "DBD_2") (pin "1") (pinfunction "K_1") (pintype "passive"))
    )
    (net (code "124") (name "Net-(DC5-A)") (class "Default")
      (node (ref "DC5") (pin "2") (pinfunction "A_2") (pintype "passive"))
      (node (ref "RC5A") (pin "1") (pinfunction "1_1") (pintype "passive"))
      (node (ref "U1") (pin "36") (pinfunction "VC5_36") (pintype "passive"))
    )
    (net (code "125") (name "Net-(DC10-A)") (class "Default")
      (node (ref "DC10") (pin "2") (pinfunction "A_2") (pintype "passive"))
      (node (ref "RC10A") (pin "1") (pinfunction "1_1") (pintype "passive"))
      (node (ref "U1") (pin "30") (pinfunction "VC10_30") (pintype "passive"))
    )
    (net (code "126") (name "Net-(DC15-A)") (class "Default")
      (node (ref "CC15") (pin "1") (pinfunction "1_1") (pintype "passive"))
      (node (ref "DC15") (pin "2") (pinfunction "A_2") (pintype "passive"))
      (node (ref "U1") (pin "24") (pinfunction "VC15_24") (pintype "passive"))
    )
    (net (code "127") (name "Net-(DC15-K)") (class "Default")
      (node (ref "DC15") (pin "1") (pinfunction "K_1") (pintype "passive"))
      (node (ref "U1") (pin "20") (pinfunction "BAT_20") (pintype "passive"))
    )
    (net (code "128") (name "Net-(DSHUNT-A)") (class "Default")
      (node (ref "DSHUNT") (pin "2") (pinfunction "A_2") (pintype "passive"))
      (node (ref "QSHUNT") (pin "2") (pinfunction "S_2") (pintype "passive"))
      (node (ref "RSHUNT2") (pin "2") (pinfunction "2_2") (pintype "passive"))
    )
    (net (code "129") (name "Net-(DSHUNT-K)") (class "Default")
      (node (ref "DSHUNT") (pin "1") (pinfunction "K_1") (pintype "passive"))
      (node (ref "RSHUNT2") (pin "1") (pinfunction "1_1") (pintype "passive"))
      (node (ref "RSHUNT3") (pin "2") (pinfunction "2_2") (pintype "passive"))
    )
    (net (code "130") (name "Net-(DS_1-A)") (class "Default")
      (node (ref "DS_1") (pin "2") (pinfunction "A_2") (pintype "passive"))
      (node (ref "DS_2") (pin "1") (pinfunction "K_1") (pintype "passive"))
    )
    (net (code "131") (name "Net-(DS_2-A)") (class "Default")
      (node (ref "DS_2") (pin "2") (pinfunction "A_2") (pintype "passive"))
      (node (ref "DS_3") (pin "1") (pinfunction "K_1") (pintype "passive"))
    )
    (net (code "132") (name "Net-(DS_3-A)") (class "Default")
      (node (ref "DS_3") (pin "2") (pinfunction "A_2") (pintype "passive"))
      (node (ref "DS_4") (pin "1") (pinfunction "K_1") (pintype "passive"))
    )
    (net (code "133") (name "Net-(DS_4-A)") (class "Default")
      (node (ref "DS_4") (pin "2") (pinfunction "A_2") (pintype "passive"))
      (node (ref "DS_5") (pin "1") (pinfunction "K_1") (pintype "passive"))
      (node (ref "RDS_5") (pin "1") (pinfunction "1_1") (pintype "passive"))
    )
    (net (code "134") (name "Net-(DS_5-A)") (class "Default")
      (node (ref "DS_5") (pin "2") (pinfunction "A_2") (pintype "passive"))
      (node (ref "DS_6") (pin "1") (pinfunction "K_1") (pintype "passive"))
      (node (ref "RDS_5") (pin "2") (pinfunction "2_2") (pintype "passive"))
      (node (ref "RDS_6") (pin "1") (pinfunction "1_1") (pintype "passive"))
    )
    (net (code "135") (name "Net-(DS_6-A)") (class "Default")
      (node (ref "DS_6") (pin "2") (pinfunction "A_2") (pintype "passive"))
      (node (ref "RDS_6") (pin "2") (pinfunction "2_2") (pintype "passive"))
      (node (ref "RS_0") (pin "2") (pinfunction "2_2") (pintype "passive"))
      (node (ref "RS_1") (pin "2") (pinfunction "2_2") (pintype "passive"))
      (node (ref "RS_2") (pin "2") (pinfunction "2_2") (pintype "passive"))
      (node (ref "RS_3") (pin "2") (pinfunction "2_2") (pintype "passive"))
      (node (ref "RS_4") (pin "2") (pinfunction "2_2") (pintype "passive"))
      (node (ref "RS_5") (pin "2") (pinfunction "2_2") (pintype "passive"))
      (node (ref "RS_6") (pin "2") (pinfunction "2_2") (pintype "passive"))
      (node (ref "RS_7") (pin "2") (pinfunction "2_2") (pintype "passive"))
      (node (ref "RS_8") (pin "2") (pinfunction "2_2") (pintype "passive"))
      (node (ref "RS_9") (pin "2") (pinfunction "2_2") (pintype "passive"))
    )
    (net (code "136") (name "Net-(LED_1-A)") (class "Default")
      (node (ref "LED_1") (pin "2") (pinfunction "A_2") (pintype "passive"))
      (node (ref "LED_1A") (pin "2") (pinfunction "A_2") (pintype "passive"))
      (node (ref "RLED_1") (pin "1") (pinfunction "1_1") (pintype "passive"))
    )
    (net (code "137") (name "Net-(LED_2-A)") (class "Default")
      (node (ref "LED_2") (pin "2") (pinfunction "A_2") (pintype "passive"))
      (node (ref "LED_2A") (pin "2") (pinfunction "A_2") (pintype "passive"))
      (node (ref "RLED_2") (pin "1") (pinfunction "1_1") (pintype "passive"))
    )
    (net (code "138") (name "Net-(LED_3-A)") (class "Default")
      (node (ref "LED_3") (pin "2") (pinfunction "A_2") (pintype "passive"))
      (node (ref "LED_3A") (pin "2") (pinfunction "A_2") (pintype "passive"))
      (node (ref "RLED_3") (pin "1") (pinfunction "1_1") (pintype "passive"))
    )
    (net (code "139") (name "Net-(Q18-D)") (class "Default")
      (node (ref "Q18") (pin "3") (pinfunction "D_3") (pintype "passive"))
      (node (ref "Q19") (pin "1") (pinfunction "G_1") (pintype "passive"))
      (node (ref "R18") (pin "2") (pinfunction "2_2") (pintype "passive"))
      (node (ref "SW_WAKE") (pin "1") (pinfunction "1_1") (pintype "passive"))
    )
    (net (code "140") (name "Net-(Q19-S)") (class "Default")
      (node (ref "Q19") (pin "2") (pinfunction "S_2") (pintype "passive"))
      (node (ref "R18") (pin "1") (pinfunction "1_1") (pintype "passive"))
      (node (ref "RS_20") (pin "1") (pinfunction "1_1") (pintype "passive"))
      (node (ref "RS_21") (pin "1") (pinfunction "1_1") (pintype "passive"))
      (node (ref "RS_22") (pin "1") (pinfunction "1_1") (pintype "passive"))
      (node (ref "RS_23") (pin "1") (pinfunction "1_1") (pintype "passive"))
      (node (ref "RS_24") (pin "1") (pinfunction "1_1") (pintype "passive"))
      (node (ref "RS_25") (pin "1") (pinfunction "1_1") (pintype "passive"))
      (node (ref "RS_26") (pin "1") (pinfunction "1_1") (pintype "passive"))
      (node (ref "RS_27") (pin "1") (pinfunction "1_1") (pintype "passive"))
      (node (ref "RS_28") (pin "1") (pinfunction "1_1") (pintype "passive"))
      (node (ref "RS_29") (pin "1") (pinfunction "1_1") (pintype "passive"))
    )
    (net (code "141") (name "Net-(QBEN-D)") (class "Default")
      (node (ref "QBEN") (pin "3") (pinfunction "D_3") (pintype "passive"))
      (node (ref "RBEN") (pin "1") (pinfunction "1_1") (pintype "passive"))
    )
    (net (code "142") (name "Net-(QSHUNT-G)") (class "Default")
      (node (ref "QSHUNT") (pin "1") (pinfunction "G_1") (pintype "passive"))
      (node (ref "RSHUNT") (pin "2") (pinfunction "2_2") (pintype "passive"))
    )
    (net (code "143") (name "Net-(Q_3V3-G)") (class "Default")
      (node (ref "3V3R1") (pin "2") (pinfunction "2_2") (pintype "passive"))
      (node (ref "3V3R2") (pin "1") (pinfunction "1_1") (pintype "passive"))
      (node (ref "Q_3V3") (pin "1") (pinfunction "G_1") (pintype "passive"))
    )
    (net (code "144") (name "Net-(RS_0-Pad1)") (class "Default")
      (node (ref "RS_0") (pin "1") (pinfunction "1_1") (pintype "passive"))
      (node (ref "RS_10") (pin "2") (pinfunction "2_2") (pintype "passive"))
    )
    (net (code "145") (name "Net-(RS_1-Pad1)") (class "Default")
      (node (ref "RS_1") (pin "1") (pinfunction "1_1") (pintype "passive"))
      (node (ref "RS_11") (pin "2") (pinfunction "2_2") (pintype "passive"))
    )
    (net (code "146") (name "Net-(RS_10-Pad1)") (class "Default")
      (node (ref "RS_10") (pin "1") (pinfunction "1_1") (pintype "passive"))
      (node (ref "RS_20") (pin "2") (pinfunction "2_2") (pintype "passive"))
    )
    (net (code "147") (name "Net-(RS_11-Pad1)") (class "Default")
      (node (ref "RS_11") (pin "1") (pinfunction "1_1") (pintype "passive"))
      (node (ref "RS_21") (pin "2") (pinfunction "2_2") (pintype "passive"))
    )
    (net (code "148") (name "Net-(RS_12-Pad1)") (class "Default")
      (node (ref "RS_12") (pin "1") (pinfunction "1_1") (pintype "passive"))
      (node (ref "RS_22") (pin "2") (pinfunction "2_2") (pintype "passive"))
    )
    (net (code "149") (name "Net-(RS_12-Pad2)") (class "Default")
      (node (ref "RS_12") (pin "2") (pinfunction "2_2") (pintype "passive"))
      (node (ref "RS_2") (pin "1") (pinfunction "1_1") (pintype "passive"))
    )
    (net (code "150") (name "Net-(RS_13-Pad1)") (class "Default")
      (node (ref "RS_13") (pin "1") (pinfunction "1_1") (pintype "passive"))
      (node (ref "RS_23") (pin "2") (pinfunction "2_2") (pintype "passive"))
    )
    (net (code "151") (name "Net-(RS_13-Pad2)") (class "Default")
      (node (ref "RS_13") (pin "2") (pinfunction "2_2") (pintype "passive"))
      (node (ref "RS_3") (pin "1") (pinfunction "1_1") (pintype "passive"))
    )
    (net (code "152") (name "Net-(RS_14-Pad1)") (class "Default")
      (node (ref "RS_14") (pin "1") (pinfunction "1_1") (pintype "passive"))
      (node (ref "RS_24") (pin "2") (pinfunction "2_2") (pintype "passive"))
    )
    (net (code "153") (name "Net-(RS_14-Pad2)") (class "Default")
      (node (ref "RS_14") (pin "2") (pinfunction "2_2") (pintype "passive"))
      (node (ref "RS_4") (pin "1") (pinfunction "1_1") (pintype "passive"))
    )
    (net (code "154") (name "Net-(RS_15-Pad1)") (class "Default")
      (node (ref "RS_15") (pin "1") (pinfunction "1_1") (pintype "passive"))
      (node (ref "RS_25") (pin "2") (pinfunction "2_2") (pintype "passive"))
    )
    (net (code "155") (name "Net-(RS_15-Pad2)") (class "Default")
      (node (ref "RS_15") (pin "2") (pinfunction "2_2") (pintype "passive"))
      (node (ref "RS_5") (pin "1") (pinfunction "1_1") (pintype "passive"))
    )
    (net (code "156") (name "Net-(RS_16-Pad1)") (class "Default")
      (node (ref "RS_16") (pin "1") (pinfunction "1_1") (pintype "passive"))
      (node (ref "RS_26") (pin "2") (pinfunction "2_2") (pintype "passive"))
    )
    (net (code "157") (name "Net-(RS_16-Pad2)") (class "Default")
      (node (ref "RS_16") (pin "2") (pinfunction "2_2") (pintype "passive"))
      (node (ref "RS_6") (pin "1") (pinfunction "1_1") (pintype "passive"))
    )
    (net (code "158") (name "Net-(RS_17-Pad1)") (class "Default")
      (node (ref "RS_17") (pin "1") (pinfunction "1_1") (pintype "passive"))
      (node (ref "RS_27") (pin "2") (pinfunction "2_2") (pintype "passive"))
    )
    (net (code "159") (name "Net-(RS_17-Pad2)") (class "Default")
      (node (ref "RS_17") (pin "2") (pinfunction "2_2") (pintype "passive"))
      (node (ref "RS_7") (pin "1") (pinfunction "1_1") (pintype "passive"))
    )
    (net (code "160") (name "Net-(RS_18-Pad1)") (class "Default")
      (node (ref "RS_18") (pin "1") (pinfunction "1_1") (pintype "passive"))
      (node (ref "RS_28") (pin "2") (pinfunction "2_2") (pintype "passive"))
    )
    (net (code "161") (name "Net-(RS_18-Pad2)") (class "Default")
      (node (ref "RS_18") (pin "2") (pinfunction "2_2") (pintype "passive"))
      (node (ref "RS_8") (pin "1") (pinfunction "1_1") (pintype "passive"))
    )
    (net (code "162") (name "Net-(RS_19-Pad1)") (class "Default")
      (node (ref "RS_19") (pin "1") (pinfunction "1_1") (pintype "passive"))
      (node (ref "RS_29") (pin "2") (pinfunction "2_2") (pintype "passive"))
    )
    (net (code "163") (name "Net-(RS_19-Pad2)") (class "Default")
      (node (ref "RS_19") (pin "2") (pinfunction "2_2") (pintype "passive"))
      (node (ref "RS_9") (pin "1") (pinfunction "1_1") (pintype "passive"))
    )
    (net (code "164") (name "Net-(R_VBUS1-Pad1)") (class "Default")
      (node (ref "R_VBUS1") (pin "1") (pinfunction "1_1") (pintype "passive"))
      (node (ref "R_VBUS2") (pin "2") (pinfunction "2_2") (pintype "passive"))
    )
    (net (code "165") (name "Net-(U1-CAP1)") (class "Default")
      (node (ref "CAP1") (pin "1") (pinfunction "1_1") (pintype "passive"))
      (node (ref "U1") (pin "7") (pinfunction "CAP1_7") (pintype "passive"))
    )
    (net (code "166") (name "Net-(U1-CAP2)") (class "Default")
      (node (ref "CAP2") (pin "1") (pinfunction "1_1") (pintype "passive"))
      (node (ref "U1") (pin "11") (pinfunction "NC_11") (pintype "passive"))
      (node (ref "U1") (pin "12") (pinfunction "NC_12") (pintype "passive"))
      (node (ref "U1") (pin "14") (pinfunction "CAP2_14") (pintype "passive"))
    )
    (net (code "167") (name "Net-(U1-CAP3)") (class "Default")
      (node (ref "CAP3") (pin "1") (pinfunction "1_1") (pintype "passive"))
      (node (ref "U1") (pin "16") (pinfunction "NC_16") (pintype "passive"))
      (node (ref "U1") (pin "17") (pinfunction "NC_17") (pintype "passive"))
      (node (ref "U1") (pin "19") (pinfunction "CAP3_19") (pintype "passive"))
    )
    (net (code "168") (name "Net-(U1-VC0)") (class "Default")
      (node (ref "RC0") (pin "1") (pinfunction "1_1") (pintype "passive"))
      (node (ref "U1") (pin "41") (pinfunction "VC0_41") (pintype "passive"))
    )
    (net (code "169") (name "Net-(U1-VC1)") (class "Default")
      (node (ref "RC1") (pin "1") (pinfunction "1_1") (pintype "passive"))
      (node (ref "U1") (pin "40") (pinfunction "VC1_40") (pintype "passive"))
    )
    (net (code "170") (name "Net-(U1-VC2)") (class "Default")
      (node (ref "RC2") (pin "1") (pinfunction "1_1") (pintype "passive"))
      (node (ref "U1") (pin "39") (pinfunction "VC2_39") (pintype "passive"))
    )
    (net (code "171") (name "Net-(U1-VC3)") (class "Default")
      (node (ref "RC3") (pin "1") (pinfunction "1_1") (pintype "passive"))
      (node (ref "U1") (pin "38") (pinfunction "VC3_38") (pintype "passive"))
    )
    (net (code "172") (name "Net-(U1-VC4)") (class "Default")
      (node (ref "RC4") (pin "1") (pinfunction "1_1") (pintype "passive"))
      (node (ref "U1") (pin "37") (pinfunction "VC4_37") (pintype "passive"))
    )
    (net (code "173") (name "Net-(U1-VC5B)") (class "Default")
      (node (ref "RC5B") (pin "1") (pinfunction "1_1") (pintype "passive"))
      (node (ref "U1") (pin "35") (pinfunction "VC5B_35") (pintype "passive"))
    )
    (net (code "174") (name "Net-(U1-VC6)") (class "Default")
      (node (ref "RC6") (pin "1") (pinfunction "1_1") (pintype "passive"))
      (node (ref "U1") (pin "34") (pinfunction "VC6_34") (pintype "passive"))
    )
    (net (code "175") (name "Net-(U1-VC7)") (class "Default")
      (node (ref "RC7") (pin "1") (pinfunction "1_1") (pintype "passive"))
      (node (ref "U1") (pin "33") (pinfunction "VC7_33") (pintype "passive"))
    )
    (net (code "176") (name "Net-(U1-VC8)") (class "Default")
      (node (ref "RC8") (pin "1") (pinfunction "1_1") (pintype "passive"))
      (node (ref "U1") (pin "32") (pinfunction "VC8_32") (pintype "passive"))
    )
    (net (code "177") (name "Net-(U1-VC9)") (class "Default")
      (node (ref "RC9") (pin "1") (pinfunction "1_1") (pintype "passive"))
      (node (ref "U1") (pin "31") (pinfunction "VC9_31") (pintype "passive"))
    )
    (net (code "178") (name "Net-(U1-VC10B)") (class "Default")
      (node (ref "RC10B") (pin "1") (pinfunction "1_1") (pintype "passive"))
      (node (ref "U1") (pin "29") (pinfunction "VC10B_29") (pintype "passive"))
    )
    (net (code "179") (name "Net-(U1-VC11)") (class "Default")
      (node (ref "RC11") (pin "1") (pinfunction "1_1") (pintype "passive"))
      (node (ref "U1") (pin "28") (pinfunction "VC11_28") (pintype "passive"))
    )
    (net (code "180") (name "Net-(U1-VC12)") (class "Default")
      (node (ref "RC12") (pin "1") (pinfunction "1_1") (pintype "passive"))
      (node (ref "U1") (pin "27") (pinfunction "VC12_27") (pintype "passive"))
    )
    (net (code "181") (name "Net-(U1-VC13)") (class "Default")
      (node (ref "RC13") (pin "1") (pinfunction "1_1") (pintype "passive"))
      (node (ref "U1") (pin "26") (pinfunction "VC13_26") (pintype "passive"))
    )
    (net (code "182") (name "Net-(U1-VC14)") (class "Default")
      (node (ref "RC14") (pin "1") (pinfunction "1_1") (pintype "passive"))
      (node (ref "U1") (pin "25") (pinfunction "VC14_25") (pintype "passive"))
    )
    (net (code "183") (name "Net-(U100-PD0-OSC_IN)") (class "Default")
      (node (ref "C100") (pin "2") (pinfunction "2_2") (pintype "passive"))
      (node (ref "U100") (pin "5") (pinfunction "PD0-OSC_IN_5") (pintype "bidirectional"))
      (node (ref "Y100") (pin "1") (pintype "passive"))
    )
    (net (code "184") (name "Net-(U100-PD1-OSC_OUT)") (class "Default")
      (node (ref "C101") (pin "2") (pinfunction "2_2") (pintype "passive"))
      (node (ref "U100") (pin "6") (pinfunction "PD1-OSC_OUT_6") (pintype "bidirectional"))
      (node (ref "Y100") (pin "2") (pintype "passive"))
    )
    (net (code "185") (name "unconnected-(J100-SBU1-PadA8)") (class "Default")
      (node (ref "J100") (pin "A8") (pinfunction "SBU1_A8") (pintype "passive"))
    )
    (net (code "186") (name "unconnected-(J100-SBU2-PadB8)") (class "Default")
      (node (ref "J100") (pin "B8") (pinfunction "SBU2_B8") (pintype "passive"))
    )
    (net (code "187") (name "unconnected-(J101-SBU1-PadA8)") (class "Default")
      (node (ref "J101") (pin "A8") (pinfunction "SBU1_A8") (pintype "passive"))
    )
    (net (code "188") (name "unconnected-(J101-SBU2-PadB8)") (class "Default")
      (node (ref "J101") (pin "B8") (pinfunction "SBU2_B8") (pintype "passive"))
    )
    (net (code "189") (name "unconnected-(U1-CHG-Pad2)") (class "Default")
      (node (ref "U1") (pin "2") (pinfunction "CHG_2") (pintype "passive"))
    )
    (net (code "190") (name "unconnected-(U1-DSG-Pad1)") (class "Default")
      (node (ref "U1") (pin "1") (pinfunction "DSG_1") (pintype "passive"))
    )
    (net (code "191") (name "unconnected-(U1-NC-Pad21)") (class "Default")
      (node (ref "U1") (pin "21") (pinfunction "NC_21") (pintype "passive"))
    )
    (net (code "192") (name "unconnected-(U1-NC-Pad22)") (class "Default")
      (node (ref "U1") (pin "22") (pinfunction "NC_22") (pintype "passive"))
    )
    (net (code "193") (name "unconnected-(U1-NC-Pad23)") (class "Default")
      (node (ref "U1") (pin "23") (pinfunction "NC_23") (pintype "passive"))
    )
  )
)
